# SCH_Nano-2-3s-AM32-ESC_2026-05-21.net
KiCad netlist of a schematic drawn in EasyEDA
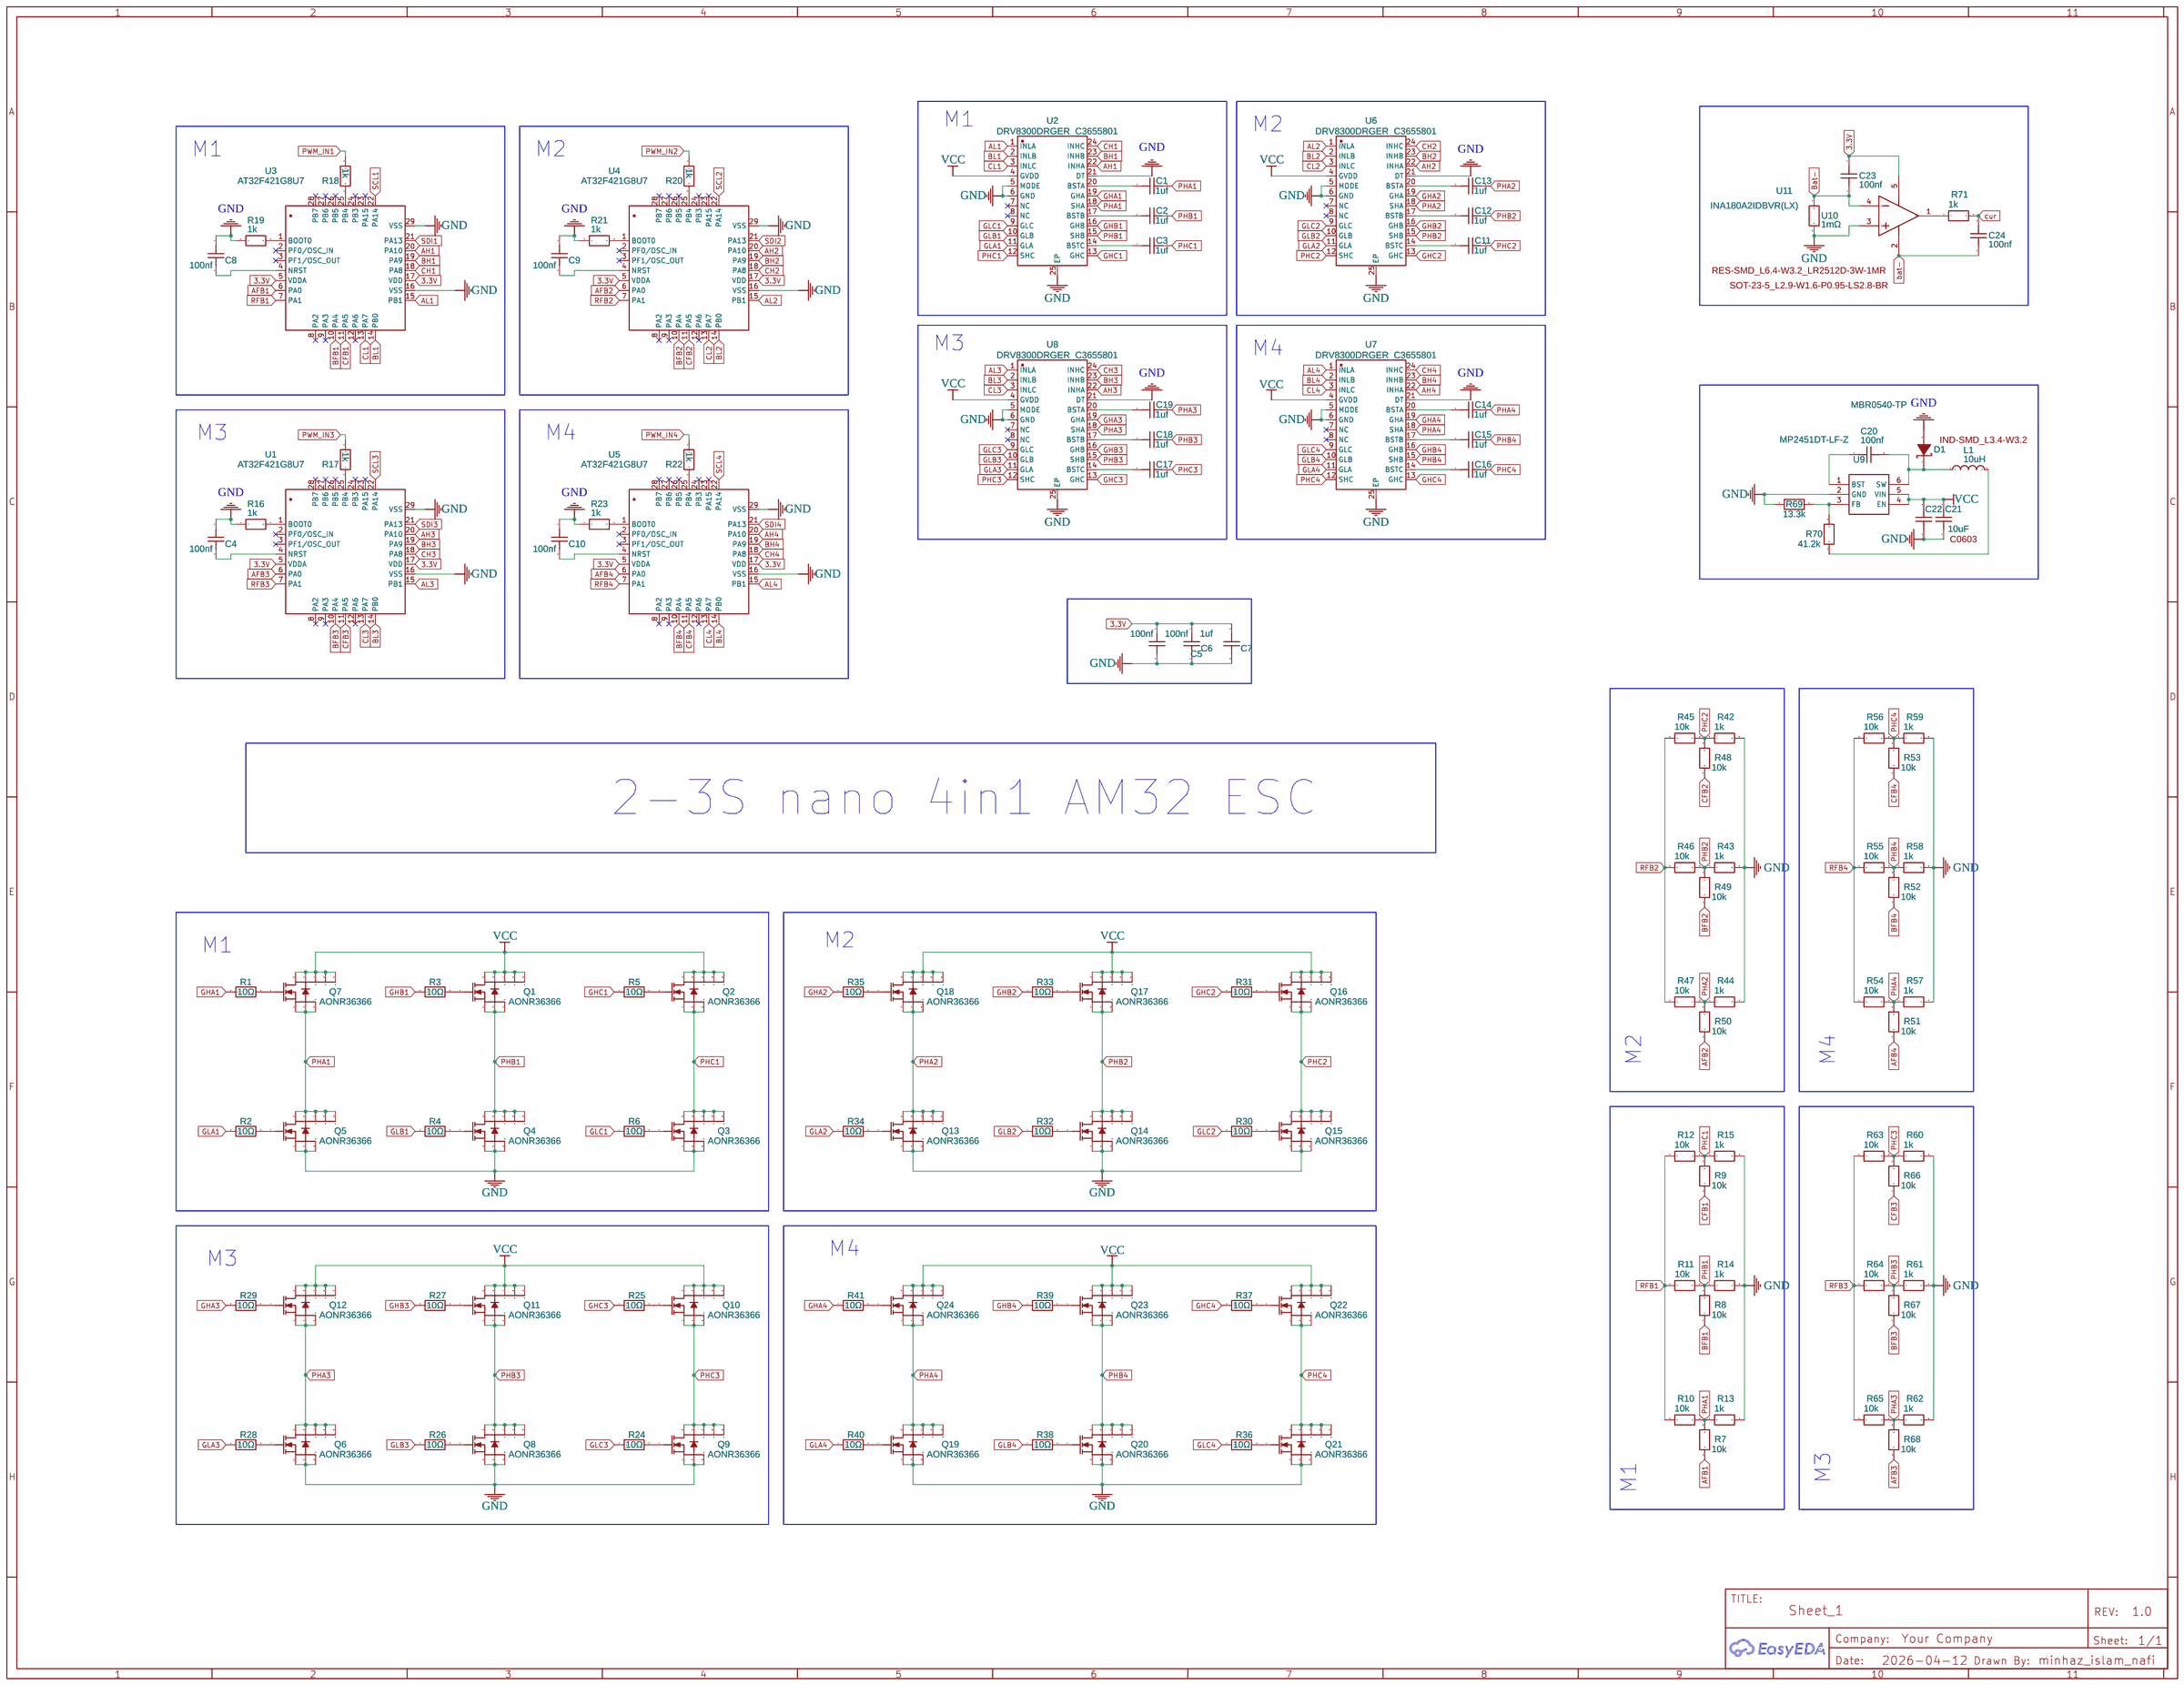
[diagram p0: schematic sheet]

(export (version "E")
  (design (tool "Eeschema 10.0.6"))
  (components
    (comp (ref "C1")
      (value "1uf")
      (fields (field (name "Manufacturer Part") "C0402C100K8GACTU"))
      (libsource (lib "") (part "C0402C100K8GACTU"))
    )
    (comp (ref "C2")
      (value "1uf")
      (fields (field (name "Manufacturer Part") "C0402C100K8GACTU"))
      (libsource (lib "") (part "C0402C100K8GACTU"))
    )
    (comp (ref "C3")
      (value "1uf")
      (fields (field (name "Manufacturer Part") "C0402C100K8GACTU"))
      (libsource (lib "") (part "C0402C100K8GACTU"))
    )
    (comp (ref "C4")
      (value "100nf")
      (fields (field (name "Manufacturer Part") "C0402C100K8GACTU"))
      (libsource (lib "") (part "C0402C100K8GACTU_2"))
    )
    (comp (ref "C5")
      (value "100nf")
      (fields (field (name "Manufacturer Part") "C0402C100K8GACTU"))
      (libsource (lib "") (part "C0402C100K8GACTU_2"))
    )
    (comp (ref "C6")
      (value "100nf")
      (fields (field (name "Manufacturer Part") "C0402C100K8GACTU"))
      (libsource (lib "") (part "C0402C100K8GACTU_2"))
    )
    (comp (ref "C7")
      (value "1uf")
      (fields (field (name "Manufacturer Part") "C0402C100K8GACTU"))
      (libsource (lib "") (part "C0402C100K8GACTU_2"))
    )
    (comp (ref "C8")
      (value "100nf")
      (fields (field (name "Manufacturer Part") "C0402C100K8GACTU"))
      (libsource (lib "") (part "C0402C100K8GACTU_2"))
    )
    (comp (ref "C9")
      (value "100nf")
      (fields (field (name "Manufacturer Part") "C0402C100K8GACTU"))
      (libsource (lib "") (part "C0402C100K8GACTU_2"))
    )
    (comp (ref "C10")
      (value "100nf")
      (fields (field (name "Manufacturer Part") "C0402C100K8GACTU"))
      (libsource (lib "") (part "C0402C100K8GACTU_2"))
    )
    (comp (ref "C11")
      (value "1uf")
      (fields (field (name "Manufacturer Part") "C0402C100K8GACTU"))
      (libsource (lib "") (part "C0402C100K8GACTU"))
    )
    (comp (ref "C12")
      (value "1uf")
      (fields (field (name "Manufacturer Part") "C0402C100K8GACTU"))
      (libsource (lib "") (part "C0402C100K8GACTU"))
    )
    (comp (ref "C13")
      (value "1uf")
      (fields (field (name "Manufacturer Part") "C0402C100K8GACTU"))
      (libsource (lib "") (part "C0402C100K8GACTU"))
    )
    (comp (ref "C14")
      (value "1uf")
      (fields (field (name "Manufacturer Part") "C0402C100K8GACTU"))
      (libsource (lib "") (part "C0402C100K8GACTU"))
    )
    (comp (ref "C15")
      (value "1uf")
      (fields (field (name "Manufacturer Part") "C0402C100K8GACTU"))
      (libsource (lib "") (part "C0402C100K8GACTU"))
    )
    (comp (ref "C16")
      (value "1uf")
      (fields (field (name "Manufacturer Part") "C0402C100K8GACTU"))
      (libsource (lib "") (part "C0402C100K8GACTU"))
    )
    (comp (ref "C17")
      (value "1uf")
      (fields (field (name "Manufacturer Part") "C0402C100K8GACTU"))
      (libsource (lib "") (part "C0402C100K8GACTU"))
    )
    (comp (ref "C18")
      (value "1uf")
      (fields (field (name "Manufacturer Part") "C0402C100K8GACTU"))
      (libsource (lib "") (part "C0402C100K8GACTU"))
    )
    (comp (ref "C19")
      (value "1uf")
      (fields (field (name "Manufacturer Part") "C0402C100K8GACTU"))
      (libsource (lib "") (part "C0402C100K8GACTU"))
    )
    (comp (ref "C20")
      (value "100nf")
      (fields (field (name "Manufacturer Part") "C0402C100K8GACTU"))
      (libsource (lib "") (part "C0402C100K8GACTU"))
    )
    (comp (ref "C21")
      (value "10uF")
      (fields
        (field (name "Manufacturer Part") "FCC0603X106K100CT")
        (field (name "Manufacturer") "FOJAN(富捷)")
      )
      (libsource (lib "") (part "FCC0603X106K100CT_1"))
    )
    (comp (ref "C22")
      (value "10uF")
      (fields
        (field (name "Manufacturer Part") "FCC0603X106K100CT")
        (field (name "Manufacturer") "FOJAN(富捷)")
      )
      (libsource (lib "") (part "FCC0603X106K100CT"))
    )
    (comp (ref "C23")
      (value "100nf")
      (fields (field (name "Manufacturer Part") "C0402C100K8GACTU"))
      (libsource (lib "") (part "C0402C100K8GACTU_1"))
    )
    (comp (ref "C24")
      (value "100nf")
      (fields (field (name "Manufacturer Part") "C0402C100K8GACTU"))
      (libsource (lib "") (part "C0402C100K8GACTU_1"))
    )
    (comp (ref "D1")
      (value "MBR0540-TP")
      (fields (field (name "Manufacturer") "MCC(美微科)"))
      (libsource (lib "") (part "MBR0540-TP"))
    )
    (comp (ref "L1")
      (value "10uH")
      (fields (field (name "Manufacturer Part") "MDE0320-100M") (field (name "Manufacturer") "KOHERelec(科或)"))
      (libsource (lib "") (part "MDE0320-100M"))
    )
    (comp (ref "Q1")
      (value "AONR36366")
      (fields (field (name "Manufacturer") "AOS"))
      (libsource (lib "") (part "AONR36366"))
    )
    (comp (ref "Q2")
      (value "AONR36366")
      (fields (field (name "Manufacturer") "AOS"))
      (libsource (lib "") (part "AONR36366"))
    )
    (comp (ref "Q3")
      (value "AONR36366")
      (fields (field (name "Manufacturer") "AOS"))
      (libsource (lib "") (part "AONR36366"))
    )
    (comp (ref "Q4")
      (value "AONR36366")
      (fields (field (name "Manufacturer") "AOS"))
      (libsource (lib "") (part "AONR36366"))
    )
    (comp (ref "Q5")
      (value "AONR36366")
      (fields (field (name "Manufacturer") "AOS"))
      (libsource (lib "") (part "AONR36366"))
    )
    (comp (ref "Q6")
      (value "AONR36366")
      (fields (field (name "Manufacturer") "AOS"))
      (libsource (lib "") (part "AONR36366"))
    )
    (comp (ref "Q7")
      (value "AONR36366")
      (fields (field (name "Manufacturer") "AOS"))
      (libsource (lib "") (part "AONR36366"))
    )
    (comp (ref "Q8")
      (value "AONR36366")
      (fields (field (name "Manufacturer") "AOS"))
      (libsource (lib "") (part "AONR36366"))
    )
    (comp (ref "Q9")
      (value "AONR36366")
      (fields (field (name "Manufacturer") "AOS"))
      (libsource (lib "") (part "AONR36366"))
    )
    (comp (ref "Q10")
      (value "AONR36366")
      (fields (field (name "Manufacturer") "AOS"))
      (libsource (lib "") (part "AONR36366"))
    )
    (comp (ref "Q11")
      (value "AONR36366")
      (fields (field (name "Manufacturer") "AOS"))
      (libsource (lib "") (part "AONR36366"))
    )
    (comp (ref "Q12")
      (value "AONR36366")
      (fields (field (name "Manufacturer") "AOS"))
      (libsource (lib "") (part "AONR36366"))
    )
    (comp (ref "Q13")
      (value "AONR36366")
      (fields (field (name "Manufacturer") "AOS"))
      (libsource (lib "") (part "AONR36366"))
    )
    (comp (ref "Q14")
      (value "AONR36366")
      (fields (field (name "Manufacturer") "AOS"))
      (libsource (lib "") (part "AONR36366"))
    )
    (comp (ref "Q15")
      (value "AONR36366")
      (fields (field (name "Manufacturer") "AOS"))
      (libsource (lib "") (part "AONR36366"))
    )
    (comp (ref "Q16")
      (value "AONR36366")
      (fields (field (name "Manufacturer") "AOS"))
      (libsource (lib "") (part "AONR36366"))
    )
    (comp (ref "Q17")
      (value "AONR36366")
      (fields (field (name "Manufacturer") "AOS"))
      (libsource (lib "") (part "AONR36366"))
    )
    (comp (ref "Q18")
      (value "AONR36366")
      (fields (field (name "Manufacturer") "AOS"))
      (libsource (lib "") (part "AONR36366"))
    )
    (comp (ref "Q19")
      (value "AONR36366")
      (fields (field (name "Manufacturer") "AOS"))
      (libsource (lib "") (part "AONR36366"))
    )
    (comp (ref "Q20")
      (value "AONR36366")
      (fields (field (name "Manufacturer") "AOS"))
      (libsource (lib "") (part "AONR36366"))
    )
    (comp (ref "Q21")
      (value "AONR36366")
      (fields (field (name "Manufacturer") "AOS"))
      (libsource (lib "") (part "AONR36366"))
    )
    (comp (ref "Q22")
      (value "AONR36366")
      (fields (field (name "Manufacturer") "AOS"))
      (libsource (lib "") (part "AONR36366"))
    )
    (comp (ref "Q23")
      (value "AONR36366")
      (fields (field (name "Manufacturer") "AOS"))
      (libsource (lib "") (part "AONR36366"))
    )
    (comp (ref "Q24")
      (value "AONR36366")
      (fields (field (name "Manufacturer") "AOS"))
      (libsource (lib "") (part "AONR36366"))
    )
    (comp (ref "R1")
      (value "10Ω")
      (fields (field (name "Manufacturer Part") "0402"))
      (libsource (lib "") (part "0402"))
    )
    (comp (ref "R2")
      (value "10Ω")
      (fields (field (name "Manufacturer Part") "0402"))
      (libsource (lib "") (part "0402"))
    )
    (comp (ref "R3")
      (value "10Ω")
      (fields (field (name "Manufacturer Part") "0402"))
      (libsource (lib "") (part "0402"))
    )
    (comp (ref "R4")
      (value "10Ω")
      (fields (field (name "Manufacturer Part") "0402"))
      (libsource (lib "") (part "0402"))
    )
    (comp (ref "R5")
      (value "10Ω")
      (fields (field (name "Manufacturer Part") "0402"))
      (libsource (lib "") (part "0402"))
    )
    (comp (ref "R6")
      (value "10Ω")
      (fields (field (name "Manufacturer Part") "0402"))
      (libsource (lib "") (part "0402"))
    )
    (comp (ref "R7")
      (value "10k")
      (fields (field (name "Manufacturer Part") "0402"))
      (libsource (lib "") (part "0402_3"))
    )
    (comp (ref "R8")
      (value "10k")
      (fields (field (name "Manufacturer Part") "0402"))
      (libsource (lib "") (part "0402_3"))
    )
    (comp (ref "R9")
      (value "10k")
      (fields (field (name "Manufacturer Part") "0402"))
      (libsource (lib "") (part "0402_3"))
    )
    (comp (ref "R10")
      (value "10k")
      (fields (field (name "Manufacturer Part") "0402"))
      (libsource (lib "") (part "0402"))
    )
    (comp (ref "R11")
      (value "10k")
      (fields (field (name "Manufacturer Part") "0402"))
      (libsource (lib "") (part "0402"))
    )
    (comp (ref "R12")
      (value "10k")
      (fields (field (name "Manufacturer Part") "0402"))
      (libsource (lib "") (part "0402"))
    )
    (comp (ref "R13")
      (value "1k")
      (fields (field (name "Manufacturer Part") "0402"))
      (libsource (lib "") (part "0402"))
    )
    (comp (ref "R14")
      (value "1k")
      (fields (field (name "Manufacturer Part") "0402"))
      (libsource (lib "") (part "0402"))
    )
    (comp (ref "R15")
      (value "1k")
      (fields (field (name "Manufacturer Part") "0402"))
      (libsource (lib "") (part "0402"))
    )
    (comp (ref "R16")
      (value "1k")
      (fields (field (name "Manufacturer Part") "0402"))
      (libsource (lib "") (part "0402"))
    )
    (comp (ref "R17")
      (value "1k")
      (fields (field (name "Manufacturer Part") "0402"))
      (libsource (lib "") (part "0402_2"))
    )
    (comp (ref "R18")
      (value "1k")
      (fields (field (name "Manufacturer Part") "0402"))
      (libsource (lib "") (part "0402_2"))
    )
    (comp (ref "R19")
      (value "1k")
      (fields (field (name "Manufacturer Part") "0402"))
      (libsource (lib "") (part "0402"))
    )
    (comp (ref "R20")
      (value "1k")
      (fields (field (name "Manufacturer Part") "0402"))
      (libsource (lib "") (part "0402_2"))
    )
    (comp (ref "R21")
      (value "1k")
      (fields (field (name "Manufacturer Part") "0402"))
      (libsource (lib "") (part "0402"))
    )
    (comp (ref "R22")
      (value "1k")
      (fields (field (name "Manufacturer Part") "0402"))
      (libsource (lib "") (part "0402_2"))
    )
    (comp (ref "R23")
      (value "1k")
      (fields (field (name "Manufacturer Part") "0402"))
      (libsource (lib "") (part "0402"))
    )
    (comp (ref "R24")
      (value "10Ω")
      (fields (field (name "Manufacturer Part") "0402"))
      (libsource (lib "") (part "0402"))
    )
    (comp (ref "R25")
      (value "10Ω")
      (fields (field (name "Manufacturer Part") "0402"))
      (libsource (lib "") (part "0402"))
    )
    (comp (ref "R26")
      (value "10Ω")
      (fields (field (name "Manufacturer Part") "0402"))
      (libsource (lib "") (part "0402"))
    )
    (comp (ref "R27")
      (value "10Ω")
      (fields (field (name "Manufacturer Part") "0402"))
      (libsource (lib "") (part "0402"))
    )
    (comp (ref "R28")
      (value "10Ω")
      (fields (field (name "Manufacturer Part") "0402"))
      (libsource (lib "") (part "0402"))
    )
    (comp (ref "R29")
      (value "10Ω")
      (fields (field (name "Manufacturer Part") "0402"))
      (libsource (lib "") (part "0402"))
    )
    (comp (ref "R30")
      (value "10Ω")
      (fields (field (name "Manufacturer Part") "0402"))
      (libsource (lib "") (part "0402"))
    )
    (comp (ref "R31")
      (value "10Ω")
      (fields (field (name "Manufacturer Part") "0402"))
      (libsource (lib "") (part "0402"))
    )
    (comp (ref "R32")
      (value "10Ω")
      (fields (field (name "Manufacturer Part") "0402"))
      (libsource (lib "") (part "0402"))
    )
    (comp (ref "R33")
      (value "10Ω")
      (fields (field (name "Manufacturer Part") "0402"))
      (libsource (lib "") (part "0402"))
    )
    (comp (ref "R34")
      (value "10Ω")
      (fields (field (name "Manufacturer Part") "0402"))
      (libsource (lib "") (part "0402"))
    )
    (comp (ref "R35")
      (value "10Ω")
      (fields (field (name "Manufacturer Part") "0402"))
      (libsource (lib "") (part "0402"))
    )
    (comp (ref "R36")
      (value "10Ω")
      (fields (field (name "Manufacturer Part") "0402"))
      (libsource (lib "") (part "0402"))
    )
    (comp (ref "R37")
      (value "10Ω")
      (fields (field (name "Manufacturer Part") "0402"))
      (libsource (lib "") (part "0402"))
    )
    (comp (ref "R38")
      (value "10Ω")
      (fields (field (name "Manufacturer Part") "0402"))
      (libsource (lib "") (part "0402"))
    )
    (comp (ref "R39")
      (value "10Ω")
      (fields (field (name "Manufacturer Part") "0402"))
      (libsource (lib "") (part "0402"))
    )
    (comp (ref "R40")
      (value "10Ω")
      (fields (field (name "Manufacturer Part") "0402"))
      (libsource (lib "") (part "0402"))
    )
    (comp (ref "R41")
      (value "10Ω")
      (fields (field (name "Manufacturer Part") "0402"))
      (libsource (lib "") (part "0402"))
    )
    (comp (ref "R42")
      (value "1k")
      (fields (field (name "Manufacturer Part") "0402"))
      (libsource (lib "") (part "0402"))
    )
    (comp (ref "R43")
      (value "1k")
      (fields (field (name "Manufacturer Part") "0402"))
      (libsource (lib "") (part "0402"))
    )
    (comp (ref "R44")
      (value "1k")
      (fields (field (name "Manufacturer Part") "0402"))
      (libsource (lib "") (part "0402"))
    )
    (comp (ref "R45")
      (value "10k")
      (fields (field (name "Manufacturer Part") "0402"))
      (libsource (lib "") (part "0402"))
    )
    (comp (ref "R46")
      (value "10k")
      (fields (field (name "Manufacturer Part") "0402"))
      (libsource (lib "") (part "0402"))
    )
    (comp (ref "R47")
      (value "10k")
      (fields (field (name "Manufacturer Part") "0402"))
      (libsource (lib "") (part "0402"))
    )
    (comp (ref "R48")
      (value "10k")
      (fields (field (name "Manufacturer Part") "0402"))
      (libsource (lib "") (part "0402_3"))
    )
    (comp (ref "R49")
      (value "10k")
      (fields (field (name "Manufacturer Part") "0402"))
      (libsource (lib "") (part "0402_3"))
    )
    (comp (ref "R50")
      (value "10k")
      (fields (field (name "Manufacturer Part") "0402"))
      (libsource (lib "") (part "0402_3"))
    )
    (comp (ref "R51")
      (value "10k")
      (fields (field (name "Manufacturer Part") "0402"))
      (libsource (lib "") (part "0402_3"))
    )
    (comp (ref "R52")
      (value "10k")
      (fields (field (name "Manufacturer Part") "0402"))
      (libsource (lib "") (part "0402_3"))
    )
    (comp (ref "R53")
      (value "10k")
      (fields (field (name "Manufacturer Part") "0402"))
      (libsource (lib "") (part "0402_3"))
    )
    (comp (ref "R54")
      (value "10k")
      (fields (field (name "Manufacturer Part") "0402"))
      (libsource (lib "") (part "0402"))
    )
    (comp (ref "R55")
      (value "10k")
      (fields (field (name "Manufacturer Part") "0402"))
      (libsource (lib "") (part "0402"))
    )
    (comp (ref "R56")
      (value "10k")
      (fields (field (name "Manufacturer Part") "0402"))
      (libsource (lib "") (part "0402"))
    )
    (comp (ref "R57")
      (value "1k")
      (fields (field (name "Manufacturer Part") "0402"))
      (libsource (lib "") (part "0402"))
    )
    (comp (ref "R58")
      (value "1k")
      (fields (field (name "Manufacturer Part") "0402"))
      (libsource (lib "") (part "0402"))
    )
    (comp (ref "R59")
      (value "1k")
      (fields (field (name "Manufacturer Part") "0402"))
      (libsource (lib "") (part "0402"))
    )
    (comp (ref "R60")
      (value "1k")
      (fields (field (name "Manufacturer Part") "0402"))
      (libsource (lib "") (part "0402"))
    )
    (comp (ref "R61")
      (value "1k")
      (fields (field (name "Manufacturer Part") "0402"))
      (libsource (lib "") (part "0402"))
    )
    (comp (ref "R62")
      (value "1k")
      (fields (field (name "Manufacturer Part") "0402"))
      (libsource (lib "") (part "0402"))
    )
    (comp (ref "R63")
      (value "10k")
      (fields (field (name "Manufacturer Part") "0402"))
      (libsource (lib "") (part "0402"))
    )
    (comp (ref "R64")
      (value "10k")
      (fields (field (name "Manufacturer Part") "0402"))
      (libsource (lib "") (part "0402"))
    )
    (comp (ref "R65")
      (value "10k")
      (fields (field (name "Manufacturer Part") "0402"))
      (libsource (lib "") (part "0402"))
    )
    (comp (ref "R66")
      (value "10k")
      (fields (field (name "Manufacturer Part") "0402"))
      (libsource (lib "") (part "0402_3"))
    )
    (comp (ref "R67")
      (value "10k")
      (fields (field (name "Manufacturer Part") "0402"))
      (libsource (lib "") (part "0402_3"))
    )
    (comp (ref "R68")
      (value "10k")
      (fields (field (name "Manufacturer Part") "0402"))
      (libsource (lib "") (part "0402_3"))
    )
    (comp (ref "R69")
      (value "13.3k")
      (fields (field (name "Manufacturer Part") "0402"))
      (libsource (lib "") (part "0402_1"))
    )
    (comp (ref "R70")
      (value "41.2k")
      (fields (field (name "Manufacturer Part") "0402"))
      (libsource (lib "") (part "0402_3"))
    )
    (comp (ref "R71")
      (value "1k")
      (fields (field (name "Manufacturer Part") "0402"))
      (libsource (lib "") (part "0402"))
    )
    (comp (ref "U1")
      (value "AT32F421G8U7")
      (fields (field (name "Manufacturer") "ARTERY(雅特力)"))
      (libsource (lib "") (part "AT32F421G8U7"))
    )
    (comp (ref "U2")
      (value "DRV8300DRGER_C3655801")
      (fields (field (name "Manufacturer Part") "DRV8300DRGER") (field (name "Manufacturer") "TI(德州仪器)"))
      (libsource (lib "") (part "DRV8300DRGER_C3655801"))
    )
    (comp (ref "U3")
      (value "AT32F421G8U7")
      (fields (field (name "Manufacturer") "ARTERY(雅特力)"))
      (libsource (lib "") (part "AT32F421G8U7"))
    )
    (comp (ref "U4")
      (value "AT32F421G8U7")
      (fields (field (name "Manufacturer") "ARTERY(雅特力)"))
      (libsource (lib "") (part "AT32F421G8U7"))
    )
    (comp (ref "U5")
      (value "AT32F421G8U7")
      (fields (field (name "Manufacturer") "ARTERY(雅特力)"))
      (libsource (lib "") (part "AT32F421G8U7"))
    )
    (comp (ref "U6")
      (value "DRV8300DRGER_C3655801")
      (fields (field (name "Manufacturer Part") "DRV8300DRGER") (field (name "Manufacturer") "TI(德州仪器)"))
      (libsource (lib "") (part "DRV8300DRGER_C3655801"))
    )
    (comp (ref "U7")
      (value "DRV8300DRGER_C3655801")
      (fields (field (name "Manufacturer Part") "DRV8300DRGER") (field (name "Manufacturer") "TI(德州仪器)"))
      (libsource (lib "") (part "DRV8300DRGER_C3655801"))
    )
    (comp (ref "U8")
      (value "DRV8300DRGER_C3655801")
      (fields (field (name "Manufacturer Part") "DRV8300DRGER") (field (name "Manufacturer") "TI(德州仪器)"))
      (libsource (lib "") (part "DRV8300DRGER_C3655801"))
    )
    (comp (ref "U9")
      (value "MP2451DT-LF-Z")
      (fields (field (name "Manufacturer") "MPS(芯源)"))
      (libsource (lib "") (part "MP2451DT-LF-Z"))
    )
    (comp (ref "U10")
      (value "1mΩ")
      (fields
        (field (name "Manufacturer Part") "PA2512FKF7W0R001E")
        (field (name "Manufacturer") "YAGEO(国巨)")
      )
      (libsource (lib "") (part "PA2512FKF7W0R001E"))
    )
    (comp (ref "U11")
      (value "INA180A2IDBVR(LX)")
      (fields (field (name "Manufacturer") "LX(灵星芯微)"))
      (libsource (lib "") (part "INA180A2IDBVR(LX)"))
    )
  )
  (nets
    (net (code "1") (name "3.3V") (class "Default")
      (node (ref "C23") (pin "2") (pinfunction "2_2") (pintype "unspecified"))
      (node (ref "C5") (pin "1") (pinfunction "1_1") (pintype "unspecified"))
      (node (ref "C6") (pin "1") (pinfunction "1_1") (pintype "unspecified"))
      (node (ref "C7") (pin "1") (pinfunction "1_1") (pintype "unspecified"))
      (node (ref "U1") (pin "17") (pinfunction "VDD_17") (pintype "unspecified"))
      (node (ref "U1") (pin "5") (pinfunction "VDDA_5") (pintype "unspecified"))
      (node (ref "U11") (pin "5") (pinfunction "VS_5") (pintype "unspecified"))
      (node (ref "U3") (pin "17") (pinfunction "VDD_17") (pintype "unspecified"))
      (node (ref "U3") (pin "5") (pinfunction "VDDA_5") (pintype "unspecified"))
      (node (ref "U4") (pin "17") (pinfunction "VDD_17") (pintype "unspecified"))
      (node (ref "U4") (pin "5") (pinfunction "VDDA_5") (pintype "unspecified"))
      (node (ref "U5") (pin "17") (pinfunction "VDD_17") (pintype "unspecified"))
      (node (ref "U5") (pin "5") (pinfunction "VDDA_5") (pintype "unspecified"))
    )
    (net (code "2") (name "AFB1") (class "Default")
      (node (ref "R7") (pin "1") (pinfunction "1_1") (pintype "unspecified"))
      (node (ref "U3") (pin "6") (pinfunction "PA0_6") (pintype "unspecified"))
    )
    (net (code "3") (name "AFB2") (class "Default")
      (node (ref "R50") (pin "1") (pinfunction "1_1") (pintype "unspecified"))
      (node (ref "U4") (pin "6") (pinfunction "PA0_6") (pintype "unspecified"))
    )
    (net (code "4") (name "AFB3") (class "Default")
      (node (ref "R68") (pin "1") (pinfunction "1_1") (pintype "unspecified"))
      (node (ref "U1") (pin "6") (pinfunction "PA0_6") (pintype "unspecified"))
    )
    (net (code "5") (name "AFB4") (class "Default")
      (node (ref "R51") (pin "1") (pinfunction "1_1") (pintype "unspecified"))
      (node (ref "U5") (pin "6") (pinfunction "PA0_6") (pintype "unspecified"))
    )
    (net (code "6") (name "AH1") (class "Default")
      (node (ref "U2") (pin "22") (pinfunction "INHA_22") (pintype "unspecified"))
      (node (ref "U3") (pin "20") (pinfunction "PA10_20") (pintype "unspecified"))
    )
    (net (code "7") (name "AH2") (class "Default")
      (node (ref "U4") (pin "20") (pinfunction "PA10_20") (pintype "unspecified"))
      (node (ref "U6") (pin "22") (pinfunction "INHA_22") (pintype "unspecified"))
    )
    (net (code "8") (name "AH3") (class "Default")
      (node (ref "U1") (pin "20") (pinfunction "PA10_20") (pintype "unspecified"))
      (node (ref "U8") (pin "22") (pinfunction "INHA_22") (pintype "unspecified"))
    )
    (net (code "9") (name "AH4") (class "Default")
      (node (ref "U5") (pin "20") (pinfunction "PA10_20") (pintype "unspecified"))
      (node (ref "U7") (pin "22") (pinfunction "INHA_22") (pintype "unspecified"))
    )
    (net (code "10") (name "AL1") (class "Default")
      (node (ref "U2") (pin "1") (pinfunction "INLA_1") (pintype "unspecified"))
      (node (ref "U3") (pin "15") (pinfunction "PB1_15") (pintype "unspecified"))
    )
    (net (code "11") (name "AL2") (class "Default")
      (node (ref "U4") (pin "15") (pinfunction "PB1_15") (pintype "unspecified"))
      (node (ref "U6") (pin "1") (pinfunction "INLA_1") (pintype "unspecified"))
    )
    (net (code "12") (name "AL3") (class "Default")
      (node (ref "U1") (pin "15") (pinfunction "PB1_15") (pintype "unspecified"))
      (node (ref "U8") (pin "1") (pinfunction "INLA_1") (pintype "unspecified"))
    )
    (net (code "13") (name "AL4") (class "Default")
      (node (ref "U5") (pin "15") (pinfunction "PB1_15") (pintype "unspecified"))
      (node (ref "U7") (pin "1") (pinfunction "INLA_1") (pintype "unspecified"))
    )
    (net (code "14") (name "BFB1") (class "Default")
      (node (ref "R8") (pin "1") (pinfunction "1_1") (pintype "unspecified"))
      (node (ref "U3") (pin "10") (pinfunction "PA4_10") (pintype "unspecified"))
    )
    (net (code "15") (name "BFB2") (class "Default")
      (node (ref "R49") (pin "1") (pinfunction "1_1") (pintype "unspecified"))
      (node (ref "U4") (pin "10") (pinfunction "PA4_10") (pintype "unspecified"))
    )
    (net (code "16") (name "BFB3") (class "Default")
      (node (ref "R67") (pin "1") (pinfunction "1_1") (pintype "unspecified"))
      (node (ref "U1") (pin "10") (pinfunction "PA4_10") (pintype "unspecified"))
    )
    (net (code "17") (name "BFB4") (class "Default")
      (node (ref "R52") (pin "1") (pinfunction "1_1") (pintype "unspecified"))
      (node (ref "U5") (pin "10") (pinfunction "PA4_10") (pintype "unspecified"))
    )
    (net (code "18") (name "BH1") (class "Default")
      (node (ref "U2") (pin "23") (pinfunction "INHB_23") (pintype "unspecified"))
      (node (ref "U3") (pin "19") (pinfunction "PA9_19") (pintype "unspecified"))
    )
    (net (code "19") (name "BH2") (class "Default")
      (node (ref "U4") (pin "19") (pinfunction "PA9_19") (pintype "unspecified"))
      (node (ref "U6") (pin "23") (pinfunction "INHB_23") (pintype "unspecified"))
    )
    (net (code "20") (name "BH3") (class "Default")
      (node (ref "U1") (pin "19") (pinfunction "PA9_19") (pintype "unspecified"))
      (node (ref "U8") (pin "23") (pinfunction "INHB_23") (pintype "unspecified"))
    )
    (net (code "21") (name "BH4") (class "Default")
      (node (ref "U5") (pin "19") (pinfunction "PA9_19") (pintype "unspecified"))
      (node (ref "U7") (pin "23") (pinfunction "INHB_23") (pintype "unspecified"))
    )
    (net (code "22") (name "BL1") (class "Default")
      (node (ref "U2") (pin "2") (pinfunction "INLB_2") (pintype "unspecified"))
      (node (ref "U3") (pin "14") (pinfunction "PB0_14") (pintype "unspecified"))
    )
    (net (code "23") (name "BL2") (class "Default")
      (node (ref "U4") (pin "14") (pinfunction "PB0_14") (pintype "unspecified"))
      (node (ref "U6") (pin "2") (pinfunction "INLB_2") (pintype "unspecified"))
    )
    (net (code "24") (name "BL3") (class "Default")
      (node (ref "U1") (pin "14") (pinfunction "PB0_14") (pintype "unspecified"))
      (node (ref "U8") (pin "2") (pinfunction "INLB_2") (pintype "unspecified"))
    )
    (net (code "25") (name "BL4") (class "Default")
      (node (ref "U5") (pin "14") (pinfunction "PB0_14") (pintype "unspecified"))
      (node (ref "U7") (pin "2") (pinfunction "INLB_2") (pintype "unspecified"))
    )
    (net (code "26") (name "Bat-") (class "Default")
      (node (ref "C23") (pin "1") (pinfunction "1_1") (pintype "unspecified"))
      (node (ref "U10") (pin "1") (pinfunction "1_1") (pintype "unspecified"))
      (node (ref "U11") (pin "4") (pinfunction "IN-_4") (pintype "unspecified"))
    )
    (net (code "27") (name "CFB1") (class "Default")
      (node (ref "R9") (pin "1") (pinfunction "1_1") (pintype "unspecified"))
      (node (ref "U3") (pin "11") (pinfunction "PA5_11") (pintype "unspecified"))
    )
    (net (code "28") (name "CFB2") (class "Default")
      (node (ref "R48") (pin "1") (pinfunction "1_1") (pintype "unspecified"))
      (node (ref "U4") (pin "11") (pinfunction "PA5_11") (pintype "unspecified"))
    )
    (net (code "29") (name "CFB3") (class "Default")
      (node (ref "R66") (pin "1") (pinfunction "1_1") (pintype "unspecified"))
      (node (ref "U1") (pin "11") (pinfunction "PA5_11") (pintype "unspecified"))
    )
    (net (code "30") (name "CFB4") (class "Default")
      (node (ref "R53") (pin "1") (pinfunction "1_1") (pintype "unspecified"))
      (node (ref "U5") (pin "11") (pinfunction "PA5_11") (pintype "unspecified"))
    )
    (net (code "31") (name "CH1") (class "Default")
      (node (ref "U2") (pin "24") (pinfunction "INHC_24") (pintype "unspecified"))
      (node (ref "U3") (pin "18") (pinfunction "PA8_18") (pintype "unspecified"))
    )
    (net (code "32") (name "CH2") (class "Default")
      (node (ref "U4") (pin "18") (pinfunction "PA8_18") (pintype "unspecified"))
      (node (ref "U6") (pin "24") (pinfunction "INHC_24") (pintype "unspecified"))
    )
    (net (code "33") (name "CH3") (class "Default")
      (node (ref "U1") (pin "18") (pinfunction "PA8_18") (pintype "unspecified"))
      (node (ref "U8") (pin "24") (pinfunction "INHC_24") (pintype "unspecified"))
    )
    (net (code "34") (name "CH4") (class "Default")
      (node (ref "U5") (pin "18") (pinfunction "PA8_18") (pintype "unspecified"))
      (node (ref "U7") (pin "24") (pinfunction "INHC_24") (pintype "unspecified"))
    )
    (net (code "35") (name "CL1") (class "Default")
      (node (ref "U2") (pin "3") (pinfunction "INLC_3") (pintype "unspecified"))
      (node (ref "U3") (pin "13") (pinfunction "PA7_13") (pintype "unspecified"))
    )
    (net (code "36") (name "CL2") (class "Default")
      (node (ref "U4") (pin "13") (pinfunction "PA7_13") (pintype "unspecified"))
      (node (ref "U6") (pin "3") (pinfunction "INLC_3") (pintype "unspecified"))
    )
    (net (code "37") (name "CL3") (class "Default")
      (node (ref "U1") (pin "13") (pinfunction "PA7_13") (pintype "unspecified"))
      (node (ref "U8") (pin "3") (pinfunction "INLC_3") (pintype "unspecified"))
    )
    (net (code "38") (name "CL4") (class "Default")
      (node (ref "U5") (pin "13") (pinfunction "PA7_13") (pintype "unspecified"))
      (node (ref "U7") (pin "3") (pinfunction "INLC_3") (pintype "unspecified"))
    )
    (net (code "39") (name "GHA1") (class "Default")
      (node (ref "R1") (pin "1") (pinfunction "1_1") (pintype "unspecified"))
      (node (ref "U2") (pin "19") (pinfunction "GHA_19") (pintype "unspecified"))
    )
    (net (code "40") (name "GHA2") (class "Default")
      (node (ref "R35") (pin "1") (pinfunction "1_1") (pintype "unspecified"))
      (node (ref "U6") (pin "19") (pinfunction "GHA_19") (pintype "unspecified"))
    )
    (net (code "41") (name "GHA3") (class "Default")
      (node (ref "R29") (pin "1") (pinfunction "1_1") (pintype "unspecified"))
      (node (ref "U8") (pin "19") (pinfunction "GHA_19") (pintype "unspecified"))
    )
    (net (code "42") (name "GHA4") (class "Default")
      (node (ref "R41") (pin "1") (pinfunction "1_1") (pintype "unspecified"))
      (node (ref "U7") (pin "19") (pinfunction "GHA_19") (pintype "unspecified"))
    )
    (net (code "43") (name "GHB1") (class "Default")
      (node (ref "R3") (pin "1") (pinfunction "1_1") (pintype "unspecified"))
      (node (ref "U2") (pin "16") (pinfunction "GHB_16") (pintype "unspecified"))
    )
    (net (code "44") (name "GHB2") (class "Default")
      (node (ref "R33") (pin "1") (pinfunction "1_1") (pintype "unspecified"))
      (node (ref "U6") (pin "16") (pinfunction "GHB_16") (pintype "unspecified"))
    )
    (net (code "45") (name "GHB3") (class "Default")
      (node (ref "R27") (pin "1") (pinfunction "1_1") (pintype "unspecified"))
      (node (ref "U8") (pin "16") (pinfunction "GHB_16") (pintype "unspecified"))
    )
    (net (code "46") (name "GHB4") (class "Default")
      (node (ref "R39") (pin "1") (pinfunction "1_1") (pintype "unspecified"))
      (node (ref "U7") (pin "16") (pinfunction "GHB_16") (pintype "unspecified"))
    )
    (net (code "47") (name "GHC1") (class "Default")
      (node (ref "R5") (pin "1") (pinfunction "1_1") (pintype "unspecified"))
      (node (ref "U2") (pin "13") (pinfunction "GHC_13") (pintype "unspecified"))
    )
    (net (code "48") (name "GHC2") (class "Default")
      (node (ref "R31") (pin "1") (pinfunction "1_1") (pintype "unspecified"))
      (node (ref "U6") (pin "13") (pinfunction "GHC_13") (pintype "unspecified"))
    )
    (net (code "49") (name "GHC3") (class "Default")
      (node (ref "R25") (pin "1") (pinfunction "1_1") (pintype "unspecified"))
      (node (ref "U8") (pin "13") (pinfunction "GHC_13") (pintype "unspecified"))
    )
    (net (code "50") (name "GHC4") (class "Default")
      (node (ref "R37") (pin "1") (pinfunction "1_1") (pintype "unspecified"))
      (node (ref "U7") (pin "13") (pinfunction "GHC_13") (pintype "unspecified"))
    )
    (net (code "51") (name "GLA1") (class "Default")
      (node (ref "R2") (pin "1") (pinfunction "1_1") (pintype "unspecified"))
      (node (ref "U2") (pin "11") (pinfunction "GLA_11") (pintype "unspecified"))
    )
    (net (code "52") (name "GLA2") (class "Default")
      (node (ref "R34") (pin "1") (pinfunction "1_1") (pintype "unspecified"))
      (node (ref "U6") (pin "11") (pinfunction "GLA_11") (pintype "unspecified"))
    )
    (net (code "53") (name "GLA3") (class "Default")
      (node (ref "R28") (pin "1") (pinfunction "1_1") (pintype "unspecified"))
      (node (ref "U8") (pin "11") (pinfunction "GLA_11") (pintype "unspecified"))
    )
    (net (code "54") (name "GLA4") (class "Default")
      (node (ref "R40") (pin "1") (pinfunction "1_1") (pintype "unspecified"))
      (node (ref "U7") (pin "11") (pinfunction "GLA_11") (pintype "unspecified"))
    )
    (net (code "55") (name "GLB1") (class "Default")
      (node (ref "R4") (pin "1") (pinfunction "1_1") (pintype "unspecified"))
      (node (ref "U2") (pin "10") (pinfunction "GLB_10") (pintype "unspecified"))
    )
    (net (code "56") (name "GLB2") (class "Default")
      (node (ref "R32") (pin "1") (pinfunction "1_1") (pintype "unspecified"))
      (node (ref "U6") (pin "10") (pinfunction "GLB_10") (pintype "unspecified"))
    )
    (net (code "57") (name "GLB3") (class "Default")
      (node (ref "R26") (pin "1") (pinfunction "1_1") (pintype "unspecified"))
      (node (ref "U8") (pin "10") (pinfunction "GLB_10") (pintype "unspecified"))
    )
    (net (code "58") (name "GLB4") (class "Default")
      (node (ref "R38") (pin "1") (pinfunction "1_1") (pintype "unspecified"))
      (node (ref "U7") (pin "10") (pinfunction "GLB_10") (pintype "unspecified"))
    )
    (net (code "59") (name "GLC1") (class "Default")
      (node (ref "R6") (pin "1") (pinfunction "1_1") (pintype "unspecified"))
      (node (ref "U2") (pin "9") (pinfunction "GLC_9") (pintype "unspecified"))
    )
    (net (code "60") (name "GLC2") (class "Default")
      (node (ref "R30") (pin "1") (pinfunction "1_1") (pintype "unspecified"))
      (node (ref "U6") (pin "9") (pinfunction "GLC_9") (pintype "unspecified"))
    )
    (net (code "61") (name "GLC3") (class "Default")
      (node (ref "R24") (pin "1") (pinfunction "1_1") (pintype "unspecified"))
      (node (ref "U8") (pin "9") (pinfunction "GLC_9") (pintype "unspecified"))
    )
    (net (code "62") (name "GLC4") (class "Default")
      (node (ref "R36") (pin "1") (pinfunction "1_1") (pintype "unspecified"))
      (node (ref "U7") (pin "9") (pinfunction "GLC_9") (pintype "unspecified"))
    )
    (net (code "63") (name "GND") (class "Default")
      (node (ref "C10") (pin "1") (pinfunction "1_1") (pintype "unspecified"))
      (node (ref "C21") (pin "1") (pinfunction "1_1") (pintype "unspecified"))
      (node (ref "C22") (pin "1") (pinfunction "1_1") (pintype "unspecified"))
      (node (ref "C4") (pin "1") (pinfunction "1_1") (pintype "unspecified"))
      (node (ref "C5") (pin "2") (pinfunction "2_2") (pintype "unspecified"))
      (node (ref "C6") (pin "2") (pinfunction "2_2") (pintype "unspecified"))
      (node (ref "C7") (pin "2") (pinfunction "2_2") (pintype "unspecified"))
      (node (ref "C8") (pin "1") (pinfunction "1_1") (pintype "unspecified"))
      (node (ref "C9") (pin "1") (pinfunction "1_1") (pintype "unspecified"))
      (node (ref "D1") (pin "2") (pinfunction "A_2") (pintype "unspecified"))
      (node (ref "Q13") (pin "1") (pinfunction "S_1") (pintype "unspecified"))
      (node (ref "Q13") (pin "2") (pinfunction "S_2") (pintype "unspecified"))
      (node (ref "Q13") (pin "3") (pinfunction "S_3") (pintype "unspecified"))
      (node (ref "Q14") (pin "1") (pinfunction "S_1") (pintype "unspecified"))
      (node (ref "Q14") (pin "2") (pinfunction "S_2") (pintype "unspecified"))
      (node (ref "Q14") (pin "3") (pinfunction "S_3") (pintype "unspecified"))
      (node (ref "Q15") (pin "1") (pinfunction "S_1") (pintype "unspecified"))
      (node (ref "Q15") (pin "2") (pinfunction "S_2") (pintype "unspecified"))
      (node (ref "Q15") (pin "3") (pinfunction "S_3") (pintype "unspecified"))
      (node (ref "Q19") (pin "1") (pinfunction "S_1") (pintype "unspecified"))
      (node (ref "Q19") (pin "2") (pinfunction "S_2") (pintype "unspecified"))
      (node (ref "Q19") (pin "3") (pinfunction "S_3") (pintype "unspecified"))
      (node (ref "Q20") (pin "1") (pinfunction "S_1") (pintype "unspecified"))
      (node (ref "Q20") (pin "2") (pinfunction "S_2") (pintype "unspecified"))
      (node (ref "Q20") (pin "3") (pinfunction "S_3") (pintype "unspecified"))
      (node (ref "Q21") (pin "1") (pinfunction "S_1") (pintype "unspecified"))
      (node (ref "Q21") (pin "2") (pinfunction "S_2") (pintype "unspecified"))
      (node (ref "Q21") (pin "3") (pinfunction "S_3") (pintype "unspecified"))
      (node (ref "Q3") (pin "1") (pinfunction "S_1") (pintype "unspecified"))
      (node (ref "Q3") (pin "2") (pinfunction "S_2") (pintype "unspecified"))
      (node (ref "Q3") (pin "3") (pinfunction "S_3") (pintype "unspecified"))
      (node (ref "Q4") (pin "1") (pinfunction "S_1") (pintype "unspecified"))
      (node (ref "Q4") (pin "2") (pinfunction "S_2") (pintype "unspecified"))
      (node (ref "Q4") (pin "3") (pinfunction "S_3") (pintype "unspecified"))
      (node (ref "Q5") (pin "1") (pinfunction "S_1") (pintype "unspecified"))
      (node (ref "Q5") (pin "2") (pinfunction "S_2") (pintype "unspecified"))
      (node (ref "Q5") (pin "3") (pinfunction "S_3") (pintype "unspecified"))
      (node (ref "Q6") (pin "1") (pinfunction "S_1") (pintype "unspecified"))
      (node (ref "Q6") (pin "2") (pinfunction "S_2") (pintype "unspecified"))
      (node (ref "Q6") (pin "3") (pinfunction "S_3") (pintype "unspecified"))
      (node (ref "Q8") (pin "1") (pinfunction "S_1") (pintype "unspecified"))
      (node (ref "Q8") (pin "2") (pinfunction "S_2") (pintype "unspecified"))
      (node (ref "Q8") (pin "3") (pinfunction "S_3") (pintype "unspecified"))
      (node (ref "Q9") (pin "1") (pinfunction "S_1") (pintype "unspecified"))
      (node (ref "Q9") (pin "2") (pinfunction "S_2") (pintype "unspecified"))
      (node (ref "Q9") (pin "3") (pinfunction "S_3") (pintype "unspecified"))
      (node (ref "R13") (pin "2") (pinfunction "2_2") (pintype "unspecified"))
      (node (ref "R14") (pin "2") (pinfunction "2_2") (pintype "unspecified"))
      (node (ref "R15") (pin "2") (pinfunction "2_2") (pintype "unspecified"))
      (node (ref "R16") (pin "1") (pinfunction "1_1") (pintype "unspecified"))
      (node (ref "R19") (pin "1") (pinfunction "1_1") (pintype "unspecified"))
      (node (ref "R21") (pin "1") (pinfunction "1_1") (pintype "unspecified"))
      (node (ref "R23") (pin "1") (pinfunction "1_1") (pintype "unspecified"))
      (node (ref "R42") (pin "2") (pinfunction "2_2") (pintype "unspecified"))
      (node (ref "R43") (pin "2") (pinfunction "2_2") (pintype "unspecified"))
      (node (ref "R44") (pin "2") (pinfunction "2_2") (pintype "unspecified"))
      (node (ref "R57") (pin "2") (pinfunction "2_2") (pintype "unspecified"))
      (node (ref "R58") (pin "2") (pinfunction "2_2") (pintype "unspecified"))
      (node (ref "R59") (pin "2") (pinfunction "2_2") (pintype "unspecified"))
      (node (ref "R60") (pin "2") (pinfunction "2_2") (pintype "unspecified"))
      (node (ref "R61") (pin "2") (pinfunction "2_2") (pintype "unspecified"))
      (node (ref "R62") (pin "2") (pinfunction "2_2") (pintype "unspecified"))
      (node (ref "R69") (pin "2") (pinfunction "2_2") (pintype "unspecified"))
      (node (ref "U1") (pin "16") (pinfunction "VSS_16") (pintype "unspecified"))
      (node (ref "U1") (pin "29") (pinfunction "VSS_29") (pintype "unspecified"))
      (node (ref "U10") (pin "2") (pinfunction "2_2") (pintype "unspecified"))
      (node (ref "U11") (pin "3") (pinfunction "IN+_3") (pintype "unspecified"))
      (node (ref "U2") (pin "21") (pinfunction "DT_21") (pintype "unspecified"))
      (node (ref "U2") (pin "25") (pinfunction "EP_25") (pintype "unspecified"))
      (node (ref "U2") (pin "5") (pinfunction "MODE_5") (pintype "unspecified"))
      (node (ref "U2") (pin "6") (pinfunction "GND_6") (pintype "unspecified"))
      (node (ref "U3") (pin "16") (pinfunction "VSS_16") (pintype "unspecified"))
      (node (ref "U3") (pin "29") (pinfunction "VSS_29") (pintype "unspecified"))
      (node (ref "U4") (pin "16") (pinfunction "VSS_16") (pintype "unspecified"))
      (node (ref "U4") (pin "29") (pinfunction "VSS_29") (pintype "unspecified"))
      (node (ref "U5") (pin "16") (pinfunction "VSS_16") (pintype "unspecified"))
      (node (ref "U5") (pin "29") (pinfunction "VSS_29") (pintype "unspecified"))
      (node (ref "U6") (pin "21") (pinfunction "DT_21") (pintype "unspecified"))
      (node (ref "U6") (pin "25") (pinfunction "EP_25") (pintype "unspecified"))
      (node (ref "U6") (pin "5") (pinfunction "MODE_5") (pintype "unspecified"))
      (node (ref "U6") (pin "6") (pinfunction "GND_6") (pintype "unspecified"))
      (node (ref "U7") (pin "21") (pinfunction "DT_21") (pintype "unspecified"))
      (node (ref "U7") (pin "25") (pinfunction "EP_25") (pintype "unspecified"))
      (node (ref "U7") (pin "5") (pinfunction "MODE_5") (pintype "unspecified"))
      (node (ref "U7") (pin "6") (pinfunction "GND_6") (pintype "unspecified"))
      (node (ref "U8") (pin "21") (pinfunction "DT_21") (pintype "unspecified"))
      (node (ref "U8") (pin "25") (pinfunction "EP_25") (pintype "unspecified"))
      (node (ref "U8") (pin "5") (pinfunction "MODE_5") (pintype "unspecified"))
      (node (ref "U8") (pin "6") (pinfunction "GND_6") (pintype "unspecified"))
      (node (ref "U9") (pin "2") (pinfunction "GND_2") (pintype "unspecified"))
    )
    (net (code "64") (name "Net-(D1-K)") (class "Default")
      (node (ref "C20") (pin "2") (pinfunction "2_2") (pintype "unspecified"))
      (node (ref "D1") (pin "1") (pinfunction "K_1") (pintype "unspecified"))
      (node (ref "L1") (pin "1") (pinfunction "1_1") (pintype "unspecified"))
      (node (ref "U9") (pin "6") (pinfunction "SW_6") (pintype "unspecified"))
    )
    (net (code "65") (name "Net-(L1-Pad2)") (class "Default")
      (node (ref "L1") (pin "2") (pinfunction "2_2") (pintype "unspecified"))
      (node (ref "R70") (pin "1") (pinfunction "1_1") (pintype "unspecified"))
    )
    (net (code "66") (name "Net-(Q1-G)") (class "Default")
      (node (ref "Q1") (pin "4") (pinfunction "G_4") (pintype "unspecified"))
      (node (ref "R3") (pin "2") (pinfunction "2_2") (pintype "unspecified"))
    )
    (net (code "67") (name "Net-(Q2-G)") (class "Default")
      (node (ref "Q2") (pin "4") (pinfunction "G_4") (pintype "unspecified"))
      (node (ref "R5") (pin "2") (pinfunction "2_2") (pintype "unspecified"))
    )
    (net (code "68") (name "Net-(Q3-G)") (class "Default")
      (node (ref "Q3") (pin "4") (pinfunction "G_4") (pintype "unspecified"))
      (node (ref "R6") (pin "2") (pinfunction "2_2") (pintype "unspecified"))
    )
    (net (code "69") (name "Net-(Q4-G)") (class "Default")
      (node (ref "Q4") (pin "4") (pinfunction "G_4") (pintype "unspecified"))
      (node (ref "R4") (pin "2") (pinfunction "2_2") (pintype "unspecified"))
    )
    (net (code "70") (name "Net-(Q5-G)") (class "Default")
      (node (ref "Q5") (pin "4") (pinfunction "G_4") (pintype "unspecified"))
      (node (ref "R2") (pin "2") (pinfunction "2_2") (pintype "unspecified"))
    )
    (net (code "71") (name "Net-(Q6-G)") (class "Default")
      (node (ref "Q6") (pin "4") (pinfunction "G_4") (pintype "unspecified"))
      (node (ref "R28") (pin "2") (pinfunction "2_2") (pintype "unspecified"))
    )
    (net (code "72") (name "Net-(Q7-G)") (class "Default")
      (node (ref "Q7") (pin "4") (pinfunction "G_4") (pintype "unspecified"))
      (node (ref "R1") (pin "2") (pinfunction "2_2") (pintype "unspecified"))
    )
    (net (code "73") (name "Net-(Q8-G)") (class "Default")
      (node (ref "Q8") (pin "4") (pinfunction "G_4") (pintype "unspecified"))
      (node (ref "R26") (pin "2") (pinfunction "2_2") (pintype "unspecified"))
    )
    (net (code "74") (name "Net-(Q9-G)") (class "Default")
      (node (ref "Q9") (pin "4") (pinfunction "G_4") (pintype "unspecified"))
      (node (ref "R24") (pin "2") (pinfunction "2_2") (pintype "unspecified"))
    )
    (net (code "75") (name "Net-(Q10-G)") (class "Default")
      (node (ref "Q10") (pin "4") (pinfunction "G_4") (pintype "unspecified"))
      (node (ref "R25") (pin "2") (pinfunction "2_2") (pintype "unspecified"))
    )
    (net (code "76") (name "Net-(Q11-G)") (class "Default")
      (node (ref "Q11") (pin "4") (pinfunction "G_4") (pintype "unspecified"))
      (node (ref "R27") (pin "2") (pinfunction "2_2") (pintype "unspecified"))
    )
    (net (code "77") (name "Net-(Q12-G)") (class "Default")
      (node (ref "Q12") (pin "4") (pinfunction "G_4") (pintype "unspecified"))
      (node (ref "R29") (pin "2") (pinfunction "2_2") (pintype "unspecified"))
    )
    (net (code "78") (name "Net-(Q13-G)") (class "Default")
      (node (ref "Q13") (pin "4") (pinfunction "G_4") (pintype "unspecified"))
      (node (ref "R34") (pin "2") (pinfunction "2_2") (pintype "unspecified"))
    )
    (net (code "79") (name "Net-(Q14-G)") (class "Default")
      (node (ref "Q14") (pin "4") (pinfunction "G_4") (pintype "unspecified"))
      (node (ref "R32") (pin "2") (pinfunction "2_2") (pintype "unspecified"))
    )
    (net (code "80") (name "Net-(Q15-G)") (class "Default")
      (node (ref "Q15") (pin "4") (pinfunction "G_4") (pintype "unspecified"))
      (node (ref "R30") (pin "2") (pinfunction "2_2") (pintype "unspecified"))
    )
    (net (code "81") (name "Net-(Q16-G)") (class "Default")
      (node (ref "Q16") (pin "4") (pinfunction "G_4") (pintype "unspecified"))
      (node (ref "R31") (pin "2") (pinfunction "2_2") (pintype "unspecified"))
    )
    (net (code "82") (name "Net-(Q17-G)") (class "Default")
      (node (ref "Q17") (pin "4") (pinfunction "G_4") (pintype "unspecified"))
      (node (ref "R33") (pin "2") (pinfunction "2_2") (pintype "unspecified"))
    )
    (net (code "83") (name "Net-(Q18-G)") (class "Default")
      (node (ref "Q18") (pin "4") (pinfunction "G_4") (pintype "unspecified"))
      (node (ref "R35") (pin "2") (pinfunction "2_2") (pintype "unspecified"))
    )
    (net (code "84") (name "Net-(Q19-G)") (class "Default")
      (node (ref "Q19") (pin "4") (pinfunction "G_4") (pintype "unspecified"))
      (node (ref "R40") (pin "2") (pinfunction "2_2") (pintype "unspecified"))
    )
    (net (code "85") (name "Net-(Q20-G)") (class "Default")
      (node (ref "Q20") (pin "4") (pinfunction "G_4") (pintype "unspecified"))
      (node (ref "R38") (pin "2") (pinfunction "2_2") (pintype "unspecified"))
    )
    (net (code "86") (name "Net-(Q21-G)") (class "Default")
      (node (ref "Q21") (pin "4") (pinfunction "G_4") (pintype "unspecified"))
      (node (ref "R36") (pin "2") (pinfunction "2_2") (pintype "unspecified"))
    )
    (net (code "87") (name "Net-(Q22-G)") (class "Default")
      (node (ref "Q22") (pin "4") (pinfunction "G_4") (pintype "unspecified"))
      (node (ref "R37") (pin "2") (pinfunction "2_2") (pintype "unspecified"))
    )
    (net (code "88") (name "Net-(Q23-G)") (class "Default")
      (node (ref "Q23") (pin "4") (pinfunction "G_4") (pintype "unspecified"))
      (node (ref "R39") (pin "2") (pinfunction "2_2") (pintype "unspecified"))
    )
    (net (code "89") (name "Net-(Q24-G)") (class "Default")
      (node (ref "Q24") (pin "4") (pinfunction "G_4") (pintype "unspecified"))
      (node (ref "R41") (pin "2") (pinfunction "2_2") (pintype "unspecified"))
    )
    (net (code "90") (name "Net-(U1-BOOT0)") (class "Default")
      (node (ref "R16") (pin "2") (pinfunction "2_2") (pintype "unspecified"))
      (node (ref "U1") (pin "1") (pinfunction "BOOT0_1") (pintype "unspecified"))
    )
    (net (code "91") (name "Net-(U1-NRST)") (class "Default")
      (node (ref "C4") (pin "2") (pinfunction "2_2") (pintype "unspecified"))
      (node (ref "U1") (pin "4") (pinfunction "NRST_4") (pintype "unspecified"))
    )
    (net (code "92") (name "Net-(U1-PB4)") (class "Default")
      (node (ref "R17") (pin "2") (pinfunction "2_2") (pintype "unspecified"))
      (node (ref "U1") (pin "25") (pinfunction "PB4_25") (pintype "unspecified"))
    )
    (net (code "93") (name "Net-(U2-BSTA)") (class "Default")
      (node (ref "C1") (pin "1") (pinfunction "1_1") (pintype "unspecified"))
      (node (ref "U2") (pin "20") (pinfunction "BSTA_20") (pintype "unspecified"))
    )
    (net (code "94") (name "Net-(U2-BSTB)") (class "Default")
      (node (ref "C2") (pin "1") (pinfunction "1_1") (pintype "unspecified"))
      (node (ref "U2") (pin "17") (pinfunction "BSTB_17") (pintype "unspecified"))
    )
    (net (code "95") (name "Net-(U2-BSTC)") (class "Default")
      (node (ref "C3") (pin "1") (pinfunction "1_1") (pintype "unspecified"))
      (node (ref "U2") (pin "14") (pinfunction "BSTC_14") (pintype "unspecified"))
    )
    (net (code "96") (name "Net-(U3-BOOT0)") (class "Default")
      (node (ref "R19") (pin "2") (pinfunction "2_2") (pintype "unspecified"))
      (node (ref "U3") (pin "1") (pinfunction "BOOT0_1") (pintype "unspecified"))
    )
    (net (code "97") (name "Net-(U3-NRST)") (class "Default")
      (node (ref "C8") (pin "2") (pinfunction "2_2") (pintype "unspecified"))
      (node (ref "U3") (pin "4") (pinfunction "NRST_4") (pintype "unspecified"))
    )
    (net (code "98") (name "Net-(U3-PB4)") (class "Default")
      (node (ref "R18") (pin "2") (pinfunction "2_2") (pintype "unspecified"))
      (node (ref "U3") (pin "25") (pinfunction "PB4_25") (pintype "unspecified"))
    )
    (net (code "99") (name "Net-(U4-BOOT0)") (class "Default")
      (node (ref "R21") (pin "2") (pinfunction "2_2") (pintype "unspecified"))
      (node (ref "U4") (pin "1") (pinfunction "BOOT0_1") (pintype "unspecified"))
    )
    (net (code "100") (name "Net-(U4-NRST)") (class "Default")
      (node (ref "C9") (pin "2") (pinfunction "2_2") (pintype "unspecified"))
      (node (ref "U4") (pin "4") (pinfunction "NRST_4") (pintype "unspecified"))
    )
    (net (code "101") (name "Net-(U4-PB4)") (class "Default")
      (node (ref "R20") (pin "2") (pinfunction "2_2") (pintype "unspecified"))
      (node (ref "U4") (pin "25") (pinfunction "PB4_25") (pintype "unspecified"))
    )
    (net (code "102") (name "Net-(U5-BOOT0)") (class "Default")
      (node (ref "R23") (pin "2") (pinfunction "2_2") (pintype "unspecified"))
      (node (ref "U5") (pin "1") (pinfunction "BOOT0_1") (pintype "unspecified"))
    )
    (net (code "103") (name "Net-(U5-NRST)") (class "Default")
      (node (ref "C10") (pin "2") (pinfunction "2_2") (pintype "unspecified"))
      (node (ref "U5") (pin "4") (pinfunction "NRST_4") (pintype "unspecified"))
    )
    (net (code "104") (name "Net-(U5-PB4)") (class "Default")
      (node (ref "R22") (pin "2") (pinfunction "2_2") (pintype "unspecified"))
      (node (ref "U5") (pin "25") (pinfunction "PB4_25") (pintype "unspecified"))
    )
    (net (code "105") (name "Net-(U6-BSTA)") (class "Default")
      (node (ref "C13") (pin "1") (pinfunction "1_1") (pintype "unspecified"))
      (node (ref "U6") (pin "20") (pinfunction "BSTA_20") (pintype "unspecified"))
    )
    (net (code "106") (name "Net-(U6-BSTB)") (class "Default")
      (node (ref "C12") (pin "1") (pinfunction "1_1") (pintype "unspecified"))
      (node (ref "U6") (pin "17") (pinfunction "BSTB_17") (pintype "unspecified"))
    )
    (net (code "107") (name "Net-(U6-BSTC)") (class "Default")
      (node (ref "C11") (pin "1") (pinfunction "1_1") (pintype "unspecified"))
      (node (ref "U6") (pin "14") (pinfunction "BSTC_14") (pintype "unspecified"))
    )
    (net (code "108") (name "Net-(U7-BSTA)") (class "Default")
      (node (ref "C14") (pin "1") (pinfunction "1_1") (pintype "unspecified"))
      (node (ref "U7") (pin "20") (pinfunction "BSTA_20") (pintype "unspecified"))
    )
    (net (code "109") (name "Net-(U7-BSTB)") (class "Default")
      (node (ref "C15") (pin "1") (pinfunction "1_1") (pintype "unspecified"))
      (node (ref "U7") (pin "17") (pinfunction "BSTB_17") (pintype "unspecified"))
    )
    (net (code "110") (name "Net-(U7-BSTC)") (class "Default")
      (node (ref "C16") (pin "1") (pinfunction "1_1") (pintype "unspecified"))
      (node (ref "U7") (pin "14") (pinfunction "BSTC_14") (pintype "unspecified"))
    )
    (net (code "111") (name "Net-(U8-BSTA)") (class "Default")
      (node (ref "C19") (pin "1") (pinfunction "1_1") (pintype "unspecified"))
      (node (ref "U8") (pin "20") (pinfunction "BSTA_20") (pintype "unspecified"))
    )
    (net (code "112") (name "Net-(U8-BSTB)") (class "Default")
      (node (ref "C18") (pin "1") (pinfunction "1_1") (pintype "unspecified"))
      (node (ref "U8") (pin "17") (pinfunction "BSTB_17") (pintype "unspecified"))
    )
    (net (code "113") (name "Net-(U8-BSTC)") (class "Default")
      (node (ref "C17") (pin "1") (pinfunction "1_1") (pintype "unspecified"))
      (node (ref "U8") (pin "14") (pinfunction "BSTC_14") (pintype "unspecified"))
    )
    (net (code "114") (name "Net-(U9-BST)") (class "Default")
      (node (ref "C20") (pin "1") (pinfunction "1_1") (pintype "unspecified"))
      (node (ref "U9") (pin "1") (pinfunction "BST_1") (pintype "unspecified"))
    )
    (net (code "115") (name "Net-(U9-FB)") (class "Default")
      (node (ref "R69") (pin "1") (pinfunction "1_1") (pintype "unspecified"))
      (node (ref "R70") (pin "2") (pinfunction "2_2") (pintype "unspecified"))
      (node (ref "U9") (pin "3") (pinfunction "FB_3") (pintype "unspecified"))
    )
    (net (code "116") (name "Net-(U11-OUT)") (class "Default")
      (node (ref "R71") (pin "1") (pinfunction "1_1") (pintype "unspecified"))
      (node (ref "U11") (pin "1") (pinfunction "OUT_1") (pintype "unspecified"))
    )
    (net (code "117") (name "PHA1") (class "Default")
      (node (ref "C1") (pin "2") (pinfunction "2_2") (pintype "unspecified"))
      (node (ref "Q5") (pin "5") (pinfunction "D_5") (pintype "unspecified"))
      (node (ref "Q5") (pin "6") (pinfunction "D_6") (pintype "unspecified"))
      (node (ref "Q5") (pin "7") (pinfunction "D_7") (pintype "unspecified"))
      (node (ref "Q5") (pin "8") (pinfunction "D_8") (pintype "unspecified"))
      (node (ref "Q5") (pin "9") (pinfunction "D_9") (pintype "unspecified"))
      (node (ref "Q7") (pin "1") (pinfunction "S_1") (pintype "unspecified"))
      (node (ref "Q7") (pin "2") (pinfunction "S_2") (pintype "unspecified"))
      (node (ref "Q7") (pin "3") (pinfunction "S_3") (pintype "unspecified"))
      (node (ref "R10") (pin "2") (pinfunction "2_2") (pintype "unspecified"))
      (node (ref "R13") (pin "1") (pinfunction "1_1") (pintype "unspecified"))
      (node (ref "R7") (pin "2") (pinfunction "2_2") (pintype "unspecified"))
      (node (ref "U2") (pin "18") (pinfunction "SHA_18") (pintype "unspecified"))
    )
    (net (code "118") (name "PHA2") (class "Default")
      (node (ref "C13") (pin "2") (pinfunction "2_2") (pintype "unspecified"))
      (node (ref "Q13") (pin "5") (pinfunction "D_5") (pintype "unspecified"))
      (node (ref "Q13") (pin "6") (pinfunction "D_6") (pintype "unspecified"))
      (node (ref "Q13") (pin "7") (pinfunction "D_7") (pintype "unspecified"))
      (node (ref "Q13") (pin "8") (pinfunction "D_8") (pintype "unspecified"))
      (node (ref "Q13") (pin "9") (pinfunction "D_9") (pintype "unspecified"))
      (node (ref "Q18") (pin "1") (pinfunction "S_1") (pintype "unspecified"))
      (node (ref "Q18") (pin "2") (pinfunction "S_2") (pintype "unspecified"))
      (node (ref "Q18") (pin "3") (pinfunction "S_3") (pintype "unspecified"))
      (node (ref "R44") (pin "1") (pinfunction "1_1") (pintype "unspecified"))
      (node (ref "R47") (pin "2") (pinfunction "2_2") (pintype "unspecified"))
      (node (ref "R50") (pin "2") (pinfunction "2_2") (pintype "unspecified"))
      (node (ref "U6") (pin "18") (pinfunction "SHA_18") (pintype "unspecified"))
    )
    (net (code "119") (name "PHA3") (class "Default")
      (node (ref "C19") (pin "2") (pinfunction "2_2") (pintype "unspecified"))
      (node (ref "Q12") (pin "1") (pinfunction "S_1") (pintype "unspecified"))
      (node (ref "Q12") (pin "2") (pinfunction "S_2") (pintype "unspecified"))
      (node (ref "Q12") (pin "3") (pinfunction "S_3") (pintype "unspecified"))
      (node (ref "Q6") (pin "5") (pinfunction "D_5") (pintype "unspecified"))
      (node (ref "Q6") (pin "6") (pinfunction "D_6") (pintype "unspecified"))
      (node (ref "Q6") (pin "7") (pinfunction "D_7") (pintype "unspecified"))
      (node (ref "Q6") (pin "8") (pinfunction "D_8") (pintype "unspecified"))
      (node (ref "Q6") (pin "9") (pinfunction "D_9") (pintype "unspecified"))
      (node (ref "R62") (pin "1") (pinfunction "1_1") (pintype "unspecified"))
      (node (ref "R65") (pin "2") (pinfunction "2_2") (pintype "unspecified"))
      (node (ref "R68") (pin "2") (pinfunction "2_2") (pintype "unspecified"))
      (node (ref "U8") (pin "18") (pinfunction "SHA_18") (pintype "unspecified"))
    )
    (net (code "120") (name "PHA4") (class "Default")
      (node (ref "C14") (pin "2") (pinfunction "2_2") (pintype "unspecified"))
      (node (ref "Q19") (pin "5") (pinfunction "D_5") (pintype "unspecified"))
      (node (ref "Q19") (pin "6") (pinfunction "D_6") (pintype "unspecified"))
      (node (ref "Q19") (pin "7") (pinfunction "D_7") (pintype "unspecified"))
      (node (ref "Q19") (pin "8") (pinfunction "D_8") (pintype "unspecified"))
      (node (ref "Q19") (pin "9") (pinfunction "D_9") (pintype "unspecified"))
      (node (ref "Q24") (pin "1") (pinfunction "S_1") (pintype "unspecified"))
      (node (ref "Q24") (pin "2") (pinfunction "S_2") (pintype "unspecified"))
      (node (ref "Q24") (pin "3") (pinfunction "S_3") (pintype "unspecified"))
      (node (ref "R51") (pin "2") (pinfunction "2_2") (pintype "unspecified"))
      (node (ref "R54") (pin "2") (pinfunction "2_2") (pintype "unspecified"))
      (node (ref "R57") (pin "1") (pinfunction "1_1") (pintype "unspecified"))
      (node (ref "U7") (pin "18") (pinfunction "SHA_18") (pintype "unspecified"))
    )
    (net (code "121") (name "PHB1") (class "Default")
      (node (ref "C2") (pin "2") (pinfunction "2_2") (pintype "unspecified"))
      (node (ref "Q1") (pin "1") (pinfunction "S_1") (pintype "unspecified"))
      (node (ref "Q1") (pin "2") (pinfunction "S_2") (pintype "unspecified"))
      (node (ref "Q1") (pin "3") (pinfunction "S_3") (pintype "unspecified"))
      (node (ref "Q4") (pin "5") (pinfunction "D_5") (pintype "unspecified"))
      (node (ref "Q4") (pin "6") (pinfunction "D_6") (pintype "unspecified"))
      (node (ref "Q4") (pin "7") (pinfunction "D_7") (pintype "unspecified"))
      (node (ref "Q4") (pin "8") (pinfunction "D_8") (pintype "unspecified"))
      (node (ref "Q4") (pin "9") (pinfunction "D_9") (pintype "unspecified"))
      (node (ref "R11") (pin "2") (pinfunction "2_2") (pintype "unspecified"))
      (node (ref "R14") (pin "1") (pinfunction "1_1") (pintype "unspecified"))
      (node (ref "R8") (pin "2") (pinfunction "2_2") (pintype "unspecified"))
      (node (ref "U2") (pin "15") (pinfunction "SHB_15") (pintype "unspecified"))
    )
    (net (code "122") (name "PHB2") (class "Default")
      (node (ref "C12") (pin "2") (pinfunction "2_2") (pintype "unspecified"))
      (node (ref "Q14") (pin "5") (pinfunction "D_5") (pintype "unspecified"))
      (node (ref "Q14") (pin "6") (pinfunction "D_6") (pintype "unspecified"))
      (node (ref "Q14") (pin "7") (pinfunction "D_7") (pintype "unspecified"))
      (node (ref "Q14") (pin "8") (pinfunction "D_8") (pintype "unspecified"))
      (node (ref "Q14") (pin "9") (pinfunction "D_9") (pintype "unspecified"))
      (node (ref "Q17") (pin "1") (pinfunction "S_1") (pintype "unspecified"))
      (node (ref "Q17") (pin "2") (pinfunction "S_2") (pintype "unspecified"))
      (node (ref "Q17") (pin "3") (pinfunction "S_3") (pintype "unspecified"))
      (node (ref "R43") (pin "1") (pinfunction "1_1") (pintype "unspecified"))
      (node (ref "R46") (pin "2") (pinfunction "2_2") (pintype "unspecified"))
      (node (ref "R49") (pin "2") (pinfunction "2_2") (pintype "unspecified"))
      (node (ref "U6") (pin "15") (pinfunction "SHB_15") (pintype "unspecified"))
    )
    (net (code "123") (name "PHB3") (class "Default")
      (node (ref "C18") (pin "2") (pinfunction "2_2") (pintype "unspecified"))
      (node (ref "Q11") (pin "1") (pinfunction "S_1") (pintype "unspecified"))
      (node (ref "Q11") (pin "2") (pinfunction "S_2") (pintype "unspecified"))
      (node (ref "Q11") (pin "3") (pinfunction "S_3") (pintype "unspecified"))
      (node (ref "Q8") (pin "5") (pinfunction "D_5") (pintype "unspecified"))
      (node (ref "Q8") (pin "6") (pinfunction "D_6") (pintype "unspecified"))
      (node (ref "Q8") (pin "7") (pinfunction "D_7") (pintype "unspecified"))
      (node (ref "Q8") (pin "8") (pinfunction "D_8") (pintype "unspecified"))
      (node (ref "Q8") (pin "9") (pinfunction "D_9") (pintype "unspecified"))
      (node (ref "R61") (pin "1") (pinfunction "1_1") (pintype "unspecified"))
      (node (ref "R64") (pin "2") (pinfunction "2_2") (pintype "unspecified"))
      (node (ref "R67") (pin "2") (pinfunction "2_2") (pintype "unspecified"))
      (node (ref "U8") (pin "15") (pinfunction "SHB_15") (pintype "unspecified"))
    )
    (net (code "124") (name "PHB4") (class "Default")
      (node (ref "C15") (pin "2") (pinfunction "2_2") (pintype "unspecified"))
      (node (ref "Q20") (pin "5") (pinfunction "D_5") (pintype "unspecified"))
      (node (ref "Q20") (pin "6") (pinfunction "D_6") (pintype "unspecified"))
      (node (ref "Q20") (pin "7") (pinfunction "D_7") (pintype "unspecified"))
      (node (ref "Q20") (pin "8") (pinfunction "D_8") (pintype "unspecified"))
      (node (ref "Q20") (pin "9") (pinfunction "D_9") (pintype "unspecified"))
      (node (ref "Q23") (pin "1") (pinfunction "S_1") (pintype "unspecified"))
      (node (ref "Q23") (pin "2") (pinfunction "S_2") (pintype "unspecified"))
      (node (ref "Q23") (pin "3") (pinfunction "S_3") (pintype "unspecified"))
      (node (ref "R52") (pin "2") (pinfunction "2_2") (pintype "unspecified"))
      (node (ref "R55") (pin "2") (pinfunction "2_2") (pintype "unspecified"))
      (node (ref "R58") (pin "1") (pinfunction "1_1") (pintype "unspecified"))
      (node (ref "U7") (pin "15") (pinfunction "SHB_15") (pintype "unspecified"))
    )
    (net (code "125") (name "PHC1") (class "Default")
      (node (ref "C3") (pin "2") (pinfunction "2_2") (pintype "unspecified"))
      (node (ref "Q2") (pin "1") (pinfunction "S_1") (pintype "unspecified"))
      (node (ref "Q2") (pin "2") (pinfunction "S_2") (pintype "unspecified"))
      (node (ref "Q2") (pin "3") (pinfunction "S_3") (pintype "unspecified"))
      (node (ref "Q3") (pin "5") (pinfunction "D_5") (pintype "unspecified"))
      (node (ref "Q3") (pin "6") (pinfunction "D_6") (pintype "unspecified"))
      (node (ref "Q3") (pin "7") (pinfunction "D_7") (pintype "unspecified"))
      (node (ref "Q3") (pin "8") (pinfunction "D_8") (pintype "unspecified"))
      (node (ref "Q3") (pin "9") (pinfunction "D_9") (pintype "unspecified"))
      (node (ref "R12") (pin "2") (pinfunction "2_2") (pintype "unspecified"))
      (node (ref "R15") (pin "1") (pinfunction "1_1") (pintype "unspecified"))
      (node (ref "R9") (pin "2") (pinfunction "2_2") (pintype "unspecified"))
      (node (ref "U2") (pin "12") (pinfunction "SHC_12") (pintype "unspecified"))
    )
    (net (code "126") (name "PHC2") (class "Default")
      (node (ref "C11") (pin "2") (pinfunction "2_2") (pintype "unspecified"))
      (node (ref "Q15") (pin "5") (pinfunction "D_5") (pintype "unspecified"))
      (node (ref "Q15") (pin "6") (pinfunction "D_6") (pintype "unspecified"))
      (node (ref "Q15") (pin "7") (pinfunction "D_7") (pintype "unspecified"))
      (node (ref "Q15") (pin "8") (pinfunction "D_8") (pintype "unspecified"))
      (node (ref "Q15") (pin "9") (pinfunction "D_9") (pintype "unspecified"))
      (node (ref "Q16") (pin "1") (pinfunction "S_1") (pintype "unspecified"))
      (node (ref "Q16") (pin "2") (pinfunction "S_2") (pintype "unspecified"))
      (node (ref "Q16") (pin "3") (pinfunction "S_3") (pintype "unspecified"))
      (node (ref "R42") (pin "1") (pinfunction "1_1") (pintype "unspecified"))
      (node (ref "R45") (pin "2") (pinfunction "2_2") (pintype "unspecified"))
      (node (ref "R48") (pin "2") (pinfunction "2_2") (pintype "unspecified"))
      (node (ref "U6") (pin "12") (pinfunction "SHC_12") (pintype "unspecified"))
    )
    (net (code "127") (name "PHC3") (class "Default")
      (node (ref "C17") (pin "2") (pinfunction "2_2") (pintype "unspecified"))
      (node (ref "Q10") (pin "1") (pinfunction "S_1") (pintype "unspecified"))
      (node (ref "Q10") (pin "2") (pinfunction "S_2") (pintype "unspecified"))
      (node (ref "Q10") (pin "3") (pinfunction "S_3") (pintype "unspecified"))
      (node (ref "Q9") (pin "5") (pinfunction "D_5") (pintype "unspecified"))
      (node (ref "Q9") (pin "6") (pinfunction "D_6") (pintype "unspecified"))
      (node (ref "Q9") (pin "7") (pinfunction "D_7") (pintype "unspecified"))
      (node (ref "Q9") (pin "8") (pinfunction "D_8") (pintype "unspecified"))
      (node (ref "Q9") (pin "9") (pinfunction "D_9") (pintype "unspecified"))
      (node (ref "R60") (pin "1") (pinfunction "1_1") (pintype "unspecified"))
      (node (ref "R63") (pin "2") (pinfunction "2_2") (pintype "unspecified"))
      (node (ref "R66") (pin "2") (pinfunction "2_2") (pintype "unspecified"))
      (node (ref "U8") (pin "12") (pinfunction "SHC_12") (pintype "unspecified"))
    )
    (net (code "128") (name "PHC4") (class "Default")
      (node (ref "C16") (pin "2") (pinfunction "2_2") (pintype "unspecified"))
      (node (ref "Q21") (pin "5") (pinfunction "D_5") (pintype "unspecified"))
      (node (ref "Q21") (pin "6") (pinfunction "D_6") (pintype "unspecified"))
      (node (ref "Q21") (pin "7") (pinfunction "D_7") (pintype "unspecified"))
      (node (ref "Q21") (pin "8") (pinfunction "D_8") (pintype "unspecified"))
      (node (ref "Q21") (pin "9") (pinfunction "D_9") (pintype "unspecified"))
      (node (ref "Q22") (pin "1") (pinfunction "S_1") (pintype "unspecified"))
      (node (ref "Q22") (pin "2") (pinfunction "S_2") (pintype "unspecified"))
      (node (ref "Q22") (pin "3") (pinfunction "S_3") (pintype "unspecified"))
      (node (ref "R53") (pin "2") (pinfunction "2_2") (pintype "unspecified"))
      (node (ref "R56") (pin "2") (pinfunction "2_2") (pintype "unspecified"))
      (node (ref "R59") (pin "1") (pinfunction "1_1") (pintype "unspecified"))
      (node (ref "U7") (pin "12") (pinfunction "SHC_12") (pintype "unspecified"))
    )
    (net (code "129") (name "PWM_IN1") (class "Default")
      (node (ref "R18") (pin "1") (pinfunction "1_1") (pintype "unspecified"))
    )
    (net (code "130") (name "PWM_IN2") (class "Default")
      (node (ref "R20") (pin "1") (pinfunction "1_1") (pintype "unspecified"))
    )
    (net (code "131") (name "PWM_IN3") (class "Default")
      (node (ref "R17") (pin "1") (pinfunction "1_1") (pintype "unspecified"))
    )
    (net (code "132") (name "PWM_IN4") (class "Default")
      (node (ref "R22") (pin "1") (pinfunction "1_1") (pintype "unspecified"))
    )
    (net (code "133") (name "RFB1") (class "Default")
      (node (ref "R10") (pin "1") (pinfunction "1_1") (pintype "unspecified"))
      (node (ref "R11") (pin "1") (pinfunction "1_1") (pintype "unspecified"))
      (node (ref "R12") (pin "1") (pinfunction "1_1") (pintype "unspecified"))
      (node (ref "U3") (pin "7") (pinfunction "PA1_7") (pintype "unspecified"))
    )
    (net (code "134") (name "RFB2") (class "Default")
      (node (ref "R45") (pin "1") (pinfunction "1_1") (pintype "unspecified"))
      (node (ref "R46") (pin "1") (pinfunction "1_1") (pintype "unspecified"))
      (node (ref "R47") (pin "1") (pinfunction "1_1") (pintype "unspecified"))
      (node (ref "U4") (pin "7") (pinfunction "PA1_7") (pintype "unspecified"))
    )
    (net (code "135") (name "RFB3") (class "Default")
      (node (ref "R63") (pin "1") (pinfunction "1_1") (pintype "unspecified"))
      (node (ref "R64") (pin "1") (pinfunction "1_1") (pintype "unspecified"))
      (node (ref "R65") (pin "1") (pinfunction "1_1") (pintype "unspecified"))
      (node (ref "U1") (pin "7") (pinfunction "PA1_7") (pintype "unspecified"))
    )
    (net (code "136") (name "RFB4") (class "Default")
      (node (ref "R54") (pin "1") (pinfunction "1_1") (pintype "unspecified"))
      (node (ref "R55") (pin "1") (pinfunction "1_1") (pintype "unspecified"))
      (node (ref "R56") (pin "1") (pinfunction "1_1") (pintype "unspecified"))
      (node (ref "U5") (pin "7") (pinfunction "PA1_7") (pintype "unspecified"))
    )
    (net (code "137") (name "SCL1") (class "Default")
      (node (ref "U3") (pin "22") (pinfunction "PA14_22") (pintype "unspecified"))
    )
    (net (code "138") (name "SCL2") (class "Default")
      (node (ref "U4") (pin "22") (pinfunction "PA14_22") (pintype "unspecified"))
    )
    (net (code "139") (name "SCL3") (class "Default")
      (node (ref "U1") (pin "22") (pinfunction "PA14_22") (pintype "unspecified"))
    )
    (net (code "140") (name "SCL4") (class "Default")
      (node (ref "U5") (pin "22") (pinfunction "PA14_22") (pintype "unspecified"))
    )
    (net (code "141") (name "SDI1") (class "Default")
      (node (ref "U3") (pin "21") (pinfunction "PA13_21") (pintype "unspecified"))
    )
    (net (code "142") (name "SDI2") (class "Default")
      (node (ref "U4") (pin "21") (pinfunction "PA13_21") (pintype "unspecified"))
    )
    (net (code "143") (name "SDI3") (class "Default")
      (node (ref "U1") (pin "21") (pinfunction "PA13_21") (pintype "unspecified"))
    )
    (net (code "144") (name "SDI4") (class "Default")
      (node (ref "U5") (pin "21") (pinfunction "PA13_21") (pintype "unspecified"))
    )
    (net (code "145") (name "VCC") (class "Default")
      (node (ref "C21") (pin "2") (pinfunction "2_2") (pintype "unspecified"))
      (node (ref "C22") (pin "2") (pinfunction "2_2") (pintype "unspecified"))
      (node (ref "Q1") (pin "5") (pinfunction "D_5") (pintype "unspecified"))
      (node (ref "Q1") (pin "6") (pinfunction "D_6") (pintype "unspecified"))
      (node (ref "Q1") (pin "7") (pinfunction "D_7") (pintype "unspecified"))
      (node (ref "Q1") (pin "8") (pinfunction "D_8") (pintype "unspecified"))
      (node (ref "Q1") (pin "9") (pinfunction "D_9") (pintype "unspecified"))
      (node (ref "Q10") (pin "5") (pinfunction "D_5") (pintype "unspecified"))
      (node (ref "Q10") (pin "6") (pinfunction "D_6") (pintype "unspecified"))
      (node (ref "Q10") (pin "7") (pinfunction "D_7") (pintype "unspecified"))
      (node (ref "Q10") (pin "8") (pinfunction "D_8") (pintype "unspecified"))
      (node (ref "Q10") (pin "9") (pinfunction "D_9") (pintype "unspecified"))
      (node (ref "Q11") (pin "5") (pinfunction "D_5") (pintype "unspecified"))
      (node (ref "Q11") (pin "6") (pinfunction "D_6") (pintype "unspecified"))
      (node (ref "Q11") (pin "7") (pinfunction "D_7") (pintype "unspecified"))
      (node (ref "Q11") (pin "8") (pinfunction "D_8") (pintype "unspecified"))
      (node (ref "Q11") (pin "9") (pinfunction "D_9") (pintype "unspecified"))
      (node (ref "Q12") (pin "5") (pinfunction "D_5") (pintype "unspecified"))
      (node (ref "Q12") (pin "6") (pinfunction "D_6") (pintype "unspecified"))
      (node (ref "Q12") (pin "7") (pinfunction "D_7") (pintype "unspecified"))
      (node (ref "Q12") (pin "8") (pinfunction "D_8") (pintype "unspecified"))
      (node (ref "Q12") (pin "9") (pinfunction "D_9") (pintype "unspecified"))
      (node (ref "Q16") (pin "5") (pinfunction "D_5") (pintype "unspecified"))
      (node (ref "Q16") (pin "6") (pinfunction "D_6") (pintype "unspecified"))
      (node (ref "Q16") (pin "7") (pinfunction "D_7") (pintype "unspecified"))
      (node (ref "Q16") (pin "8") (pinfunction "D_8") (pintype "unspecified"))
      (node (ref "Q16") (pin "9") (pinfunction "D_9") (pintype "unspecified"))
      (node (ref "Q17") (pin "5") (pinfunction "D_5") (pintype "unspecified"))
      (node (ref "Q17") (pin "6") (pinfunction "D_6") (pintype "unspecified"))
      (node (ref "Q17") (pin "7") (pinfunction "D_7") (pintype "unspecified"))
      (node (ref "Q17") (pin "8") (pinfunction "D_8") (pintype "unspecified"))
      (node (ref "Q17") (pin "9") (pinfunction "D_9") (pintype "unspecified"))
      (node (ref "Q18") (pin "5") (pinfunction "D_5") (pintype "unspecified"))
      (node (ref "Q18") (pin "6") (pinfunction "D_6") (pintype "unspecified"))
      (node (ref "Q18") (pin "7") (pinfunction "D_7") (pintype "unspecified"))
      (node (ref "Q18") (pin "8") (pinfunction "D_8") (pintype "unspecified"))
      (node (ref "Q18") (pin "9") (pinfunction "D_9") (pintype "unspecified"))
      (node (ref "Q2") (pin "5") (pinfunction "D_5") (pintype "unspecified"))
      (node (ref "Q2") (pin "6") (pinfunction "D_6") (pintype "unspecified"))
      (node (ref "Q2") (pin "7") (pinfunction "D_7") (pintype "unspecified"))
      (node (ref "Q2") (pin "8") (pinfunction "D_8") (pintype "unspecified"))
      (node (ref "Q2") (pin "9") (pinfunction "D_9") (pintype "unspecified"))
      (node (ref "Q22") (pin "5") (pinfunction "D_5") (pintype "unspecified"))
      (node (ref "Q22") (pin "6") (pinfunction "D_6") (pintype "unspecified"))
      (node (ref "Q22") (pin "7") (pinfunction "D_7") (pintype "unspecified"))
      (node (ref "Q22") (pin "8") (pinfunction "D_8") (pintype "unspecified"))
      (node (ref "Q22") (pin "9") (pinfunction "D_9") (pintype "unspecified"))
      (node (ref "Q23") (pin "5") (pinfunction "D_5") (pintype "unspecified"))
      (node (ref "Q23") (pin "6") (pinfunction "D_6") (pintype "unspecified"))
      (node (ref "Q23") (pin "7") (pinfunction "D_7") (pintype "unspecified"))
      (node (ref "Q23") (pin "8") (pinfunction "D_8") (pintype "unspecified"))
      (node (ref "Q23") (pin "9") (pinfunction "D_9") (pintype "unspecified"))
      (node (ref "Q24") (pin "5") (pinfunction "D_5") (pintype "unspecified"))
      (node (ref "Q24") (pin "6") (pinfunction "D_6") (pintype "unspecified"))
      (node (ref "Q24") (pin "7") (pinfunction "D_7") (pintype "unspecified"))
      (node (ref "Q24") (pin "8") (pinfunction "D_8") (pintype "unspecified"))
      (node (ref "Q24") (pin "9") (pinfunction "D_9") (pintype "unspecified"))
      (node (ref "Q7") (pin "5") (pinfunction "D_5") (pintype "unspecified"))
      (node (ref "Q7") (pin "6") (pinfunction "D_6") (pintype "unspecified"))
      (node (ref "Q7") (pin "7") (pinfunction "D_7") (pintype "unspecified"))
      (node (ref "Q7") (pin "8") (pinfunction "D_8") (pintype "unspecified"))
      (node (ref "Q7") (pin "9") (pinfunction "D_9") (pintype "unspecified"))
      (node (ref "U2") (pin "4") (pinfunction "GVDD_4") (pintype "unspecified"))
      (node (ref "U6") (pin "4") (pinfunction "GVDD_4") (pintype "unspecified"))
      (node (ref "U7") (pin "4") (pinfunction "GVDD_4") (pintype "unspecified"))
      (node (ref "U8") (pin "4") (pinfunction "GVDD_4") (pintype "unspecified"))
      (node (ref "U9") (pin "4") (pinfunction "EN_4") (pintype "unspecified"))
      (node (ref "U9") (pin "5") (pinfunction "VIN_5") (pintype "unspecified"))
    )
    (net (code "146") (name "bat-") (class "Default")
      (node (ref "C24") (pin "1") (pinfunction "1_1") (pintype "unspecified"))
      (node (ref "U11") (pin "2") (pinfunction "GND_2") (pintype "unspecified"))
    )
    (net (code "147") (name "cur") (class "Default")
      (node (ref "C24") (pin "2") (pinfunction "2_2") (pintype "unspecified"))
      (node (ref "R71") (pin "2") (pinfunction "2_2") (pintype "unspecified"))
    )
    (net (code "148") (name "unconnected-(U1-PA2-Pad8)") (class "Default")
      (node (ref "U1") (pin "8") (pinfunction "PA2_8") (pintype "unspecified+no_connect"))
    )
    (net (code "149") (name "unconnected-(U1-PA3-Pad9)") (class "Default")
      (node (ref "U1") (pin "9") (pinfunction "PA3_9") (pintype "unspecified+no_connect"))
    )
    (net (code "150") (name "unconnected-(U1-PA6-Pad12)") (class "Default")
      (node (ref "U1") (pin "12") (pinfunction "PA6_12") (pintype "unspecified+no_connect"))
    )
    (net (code "151") (name "unconnected-(U1-PA15-Pad23)") (class "Default")
      (node (ref "U1") (pin "23") (pinfunction "PA15_23") (pintype "unspecified+no_connect"))
    )
    (net (code "152") (name "unconnected-(U1-PB3-Pad24)") (class "Default")
      (node (ref "U1") (pin "24") (pinfunction "PB3_24") (pintype "unspecified+no_connect"))
    )
    (net (code "153") (name "unconnected-(U1-PB5-Pad26)") (class "Default")
      (node (ref "U1") (pin "26") (pinfunction "PB5_26") (pintype "unspecified+no_connect"))
    )
    (net (code "154") (name "unconnected-(U1-PB6-Pad27)") (class "Default")
      (node (ref "U1") (pin "27") (pinfunction "PB6_27") (pintype "unspecified+no_connect"))
    )
    (net (code "155") (name "unconnected-(U1-PB7-Pad28)") (class "Default")
      (node (ref "U1") (pin "28") (pinfunction "PB7_28") (pintype "unspecified+no_connect"))
    )
    (net (code "156") (name "unconnected-(U1-PF0{slash}OSC_IN-Pad2)") (class "Default")
      (node (ref "U1") (pin "2") (pinfunction "PF0/OSC_IN_2") (pintype "unspecified+no_connect"))
    )
    (net (code "157") (name "unconnected-(U1-PF1{slash}OSC_OUT-Pad3)") (class "Default")
      (node (ref "U1") (pin "3") (pinfunction "PF1/OSC_OUT_3") (pintype "unspecified+no_connect"))
    )
    (net (code "158") (name "unconnected-(U2-NC-Pad7)") (class "Default")
      (node (ref "U2") (pin "7") (pinfunction "NC_7") (pintype "unspecified+no_connect"))
    )
    (net (code "159") (name "unconnected-(U2-NC-Pad8)") (class "Default")
      (node (ref "U2") (pin "8") (pinfunction "NC_8") (pintype "unspecified+no_connect"))
    )
    (net (code "160") (name "unconnected-(U3-PA2-Pad8)") (class "Default")
      (node (ref "U3") (pin "8") (pinfunction "PA2_8") (pintype "unspecified+no_connect"))
    )
    (net (code "161") (name "unconnected-(U3-PA3-Pad9)") (class "Default")
      (node (ref "U3") (pin "9") (pinfunction "PA3_9") (pintype "unspecified+no_connect"))
    )
    (net (code "162") (name "unconnected-(U3-PA6-Pad12)") (class "Default")
      (node (ref "U3") (pin "12") (pinfunction "PA6_12") (pintype "unspecified+no_connect"))
    )
    (net (code "163") (name "unconnected-(U3-PA15-Pad23)") (class "Default")
      (node (ref "U3") (pin "23") (pinfunction "PA15_23") (pintype "unspecified+no_connect"))
    )
    (net (code "164") (name "unconnected-(U3-PB3-Pad24)") (class "Default")
      (node (ref "U3") (pin "24") (pinfunction "PB3_24") (pintype "unspecified+no_connect"))
    )
    (net (code "165") (name "unconnected-(U3-PB5-Pad26)") (class "Default")
      (node (ref "U3") (pin "26") (pinfunction "PB5_26") (pintype "unspecified+no_connect"))
    )
    (net (code "166") (name "unconnected-(U3-PB6-Pad27)") (class "Default")
      (node (ref "U3") (pin "27") (pinfunction "PB6_27") (pintype "unspecified+no_connect"))
    )
    (net (code "167") (name "unconnected-(U3-PB7-Pad28)") (class "Default")
      (node (ref "U3") (pin "28") (pinfunction "PB7_28") (pintype "unspecified+no_connect"))
    )
    (net (code "168") (name "unconnected-(U3-PF0{slash}OSC_IN-Pad2)") (class "Default")
      (node (ref "U3") (pin "2") (pinfunction "PF0/OSC_IN_2") (pintype "unspecified+no_connect"))
    )
    (net (code "169") (name "unconnected-(U3-PF1{slash}OSC_OUT-Pad3)") (class "Default")
      (node (ref "U3") (pin "3") (pinfunction "PF1/OSC_OUT_3") (pintype "unspecified+no_connect"))
    )
    (net (code "170") (name "unconnected-(U4-PA2-Pad8)") (class "Default")
      (node (ref "U4") (pin "8") (pinfunction "PA2_8") (pintype "unspecified+no_connect"))
    )
    (net (code "171") (name "unconnected-(U4-PA3-Pad9)") (class "Default")
      (node (ref "U4") (pin "9") (pinfunction "PA3_9") (pintype "unspecified+no_connect"))
    )
    (net (code "172") (name "unconnected-(U4-PA6-Pad12)") (class "Default")
      (node (ref "U4") (pin "12") (pinfunction "PA6_12") (pintype "unspecified+no_connect"))
    )
    (net (code "173") (name "unconnected-(U4-PA15-Pad23)") (class "Default")
      (node (ref "U4") (pin "23") (pinfunction "PA15_23") (pintype "unspecified+no_connect"))
    )
    (net (code "174") (name "unconnected-(U4-PB3-Pad24)") (class "Default")
      (node (ref "U4") (pin "24") (pinfunction "PB3_24") (pintype "unspecified+no_connect"))
    )
    (net (code "175") (name "unconnected-(U4-PB5-Pad26)") (class "Default")
      (node (ref "U4") (pin "26") (pinfunction "PB5_26") (pintype "unspecified+no_connect"))
    )
    (net (code "176") (name "unconnected-(U4-PB6-Pad27)") (class "Default")
      (node (ref "U4") (pin "27") (pinfunction "PB6_27") (pintype "unspecified+no_connect"))
    )
    (net (code "177") (name "unconnected-(U4-PB7-Pad28)") (class "Default")
      (node (ref "U4") (pin "28") (pinfunction "PB7_28") (pintype "unspecified+no_connect"))
    )
    (net (code "178") (name "unconnected-(U4-PF0{slash}OSC_IN-Pad2)") (class "Default")
      (node (ref "U4") (pin "2") (pinfunction "PF0/OSC_IN_2") (pintype "unspecified+no_connect"))
    )
    (net (code "179") (name "unconnected-(U4-PF1{slash}OSC_OUT-Pad3)") (class "Default")
      (node (ref "U4") (pin "3") (pinfunction "PF1/OSC_OUT_3") (pintype "unspecified+no_connect"))
    )
    (net (code "180") (name "unconnected-(U5-PA2-Pad8)") (class "Default")
      (node (ref "U5") (pin "8") (pinfunction "PA2_8") (pintype "unspecified+no_connect"))
    )
    (net (code "181") (name "unconnected-(U5-PA3-Pad9)") (class "Default")
      (node (ref "U5") (pin "9") (pinfunction "PA3_9") (pintype "unspecified+no_connect"))
    )
    (net (code "182") (name "unconnected-(U5-PA6-Pad12)") (class "Default")
      (node (ref "U5") (pin "12") (pinfunction "PA6_12") (pintype "unspecified+no_connect"))
    )
    (net (code "183") (name "unconnected-(U5-PA15-Pad23)") (class "Default")
      (node (ref "U5") (pin "23") (pinfunction "PA15_23") (pintype "unspecified+no_connect"))
    )
    (net (code "184") (name "unconnected-(U5-PB3-Pad24)") (class "Default")
      (node (ref "U5") (pin "24") (pinfunction "PB3_24") (pintype "unspecified+no_connect"))
    )
    (net (code "185") (name "unconnected-(U5-PB5-Pad26)") (class "Default")
      (node (ref "U5") (pin "26") (pinfunction "PB5_26") (pintype "unspecified+no_connect"))
    )
    (net (code "186") (name "unconnected-(U5-PB6-Pad27)") (class "Default")
      (node (ref "U5") (pin "27") (pinfunction "PB6_27") (pintype "unspecified+no_connect"))
    )
    (net (code "187") (name "unconnected-(U5-PB7-Pad28)") (class "Default")
      (node (ref "U5") (pin "28") (pinfunction "PB7_28") (pintype "unspecified+no_connect"))
    )
    (net (code "188") (name "unconnected-(U5-PF0{slash}OSC_IN-Pad2)") (class "Default")
      (node (ref "U5") (pin "2") (pinfunction "PF0/OSC_IN_2") (pintype "unspecified+no_connect"))
    )
    (net (code "189") (name "unconnected-(U5-PF1{slash}OSC_OUT-Pad3)") (class "Default")
      (node (ref "U5") (pin "3") (pinfunction "PF1/OSC_OUT_3") (pintype "unspecified+no_connect"))
    )
    (net (code "190") (name "unconnected-(U6-NC-Pad7)") (class "Default")
      (node (ref "U6") (pin "7") (pinfunction "NC_7") (pintype "unspecified+no_connect"))
    )
    (net (code "191") (name "unconnected-(U6-NC-Pad8)") (class "Default")
      (node (ref "U6") (pin "8") (pinfunction "NC_8") (pintype "unspecified+no_connect"))
    )
    (net (code "192") (name "unconnected-(U7-NC-Pad7)") (class "Default")
      (node (ref "U7") (pin "7") (pinfunction "NC_7") (pintype "unspecified+no_connect"))
    )
    (net (code "193") (name "unconnected-(U7-NC-Pad8)") (class "Default")
      (node (ref "U7") (pin "8") (pinfunction "NC_8") (pintype "unspecified+no_connect"))
    )
    (net (code "194") (name "unconnected-(U8-NC-Pad7)") (class "Default")
      (node (ref "U8") (pin "7") (pinfunction "NC_7") (pintype "unspecified+no_connect"))
    )
    (net (code "195") (name "unconnected-(U8-NC-Pad8)") (class "Default")
      (node (ref "U8") (pin "8") (pinfunction "NC_8") (pintype "unspecified+no_connect"))
    )
  )
)
